# Dx32_V1_1.net
KiCad netlist of a schematic drawn in EAGLE
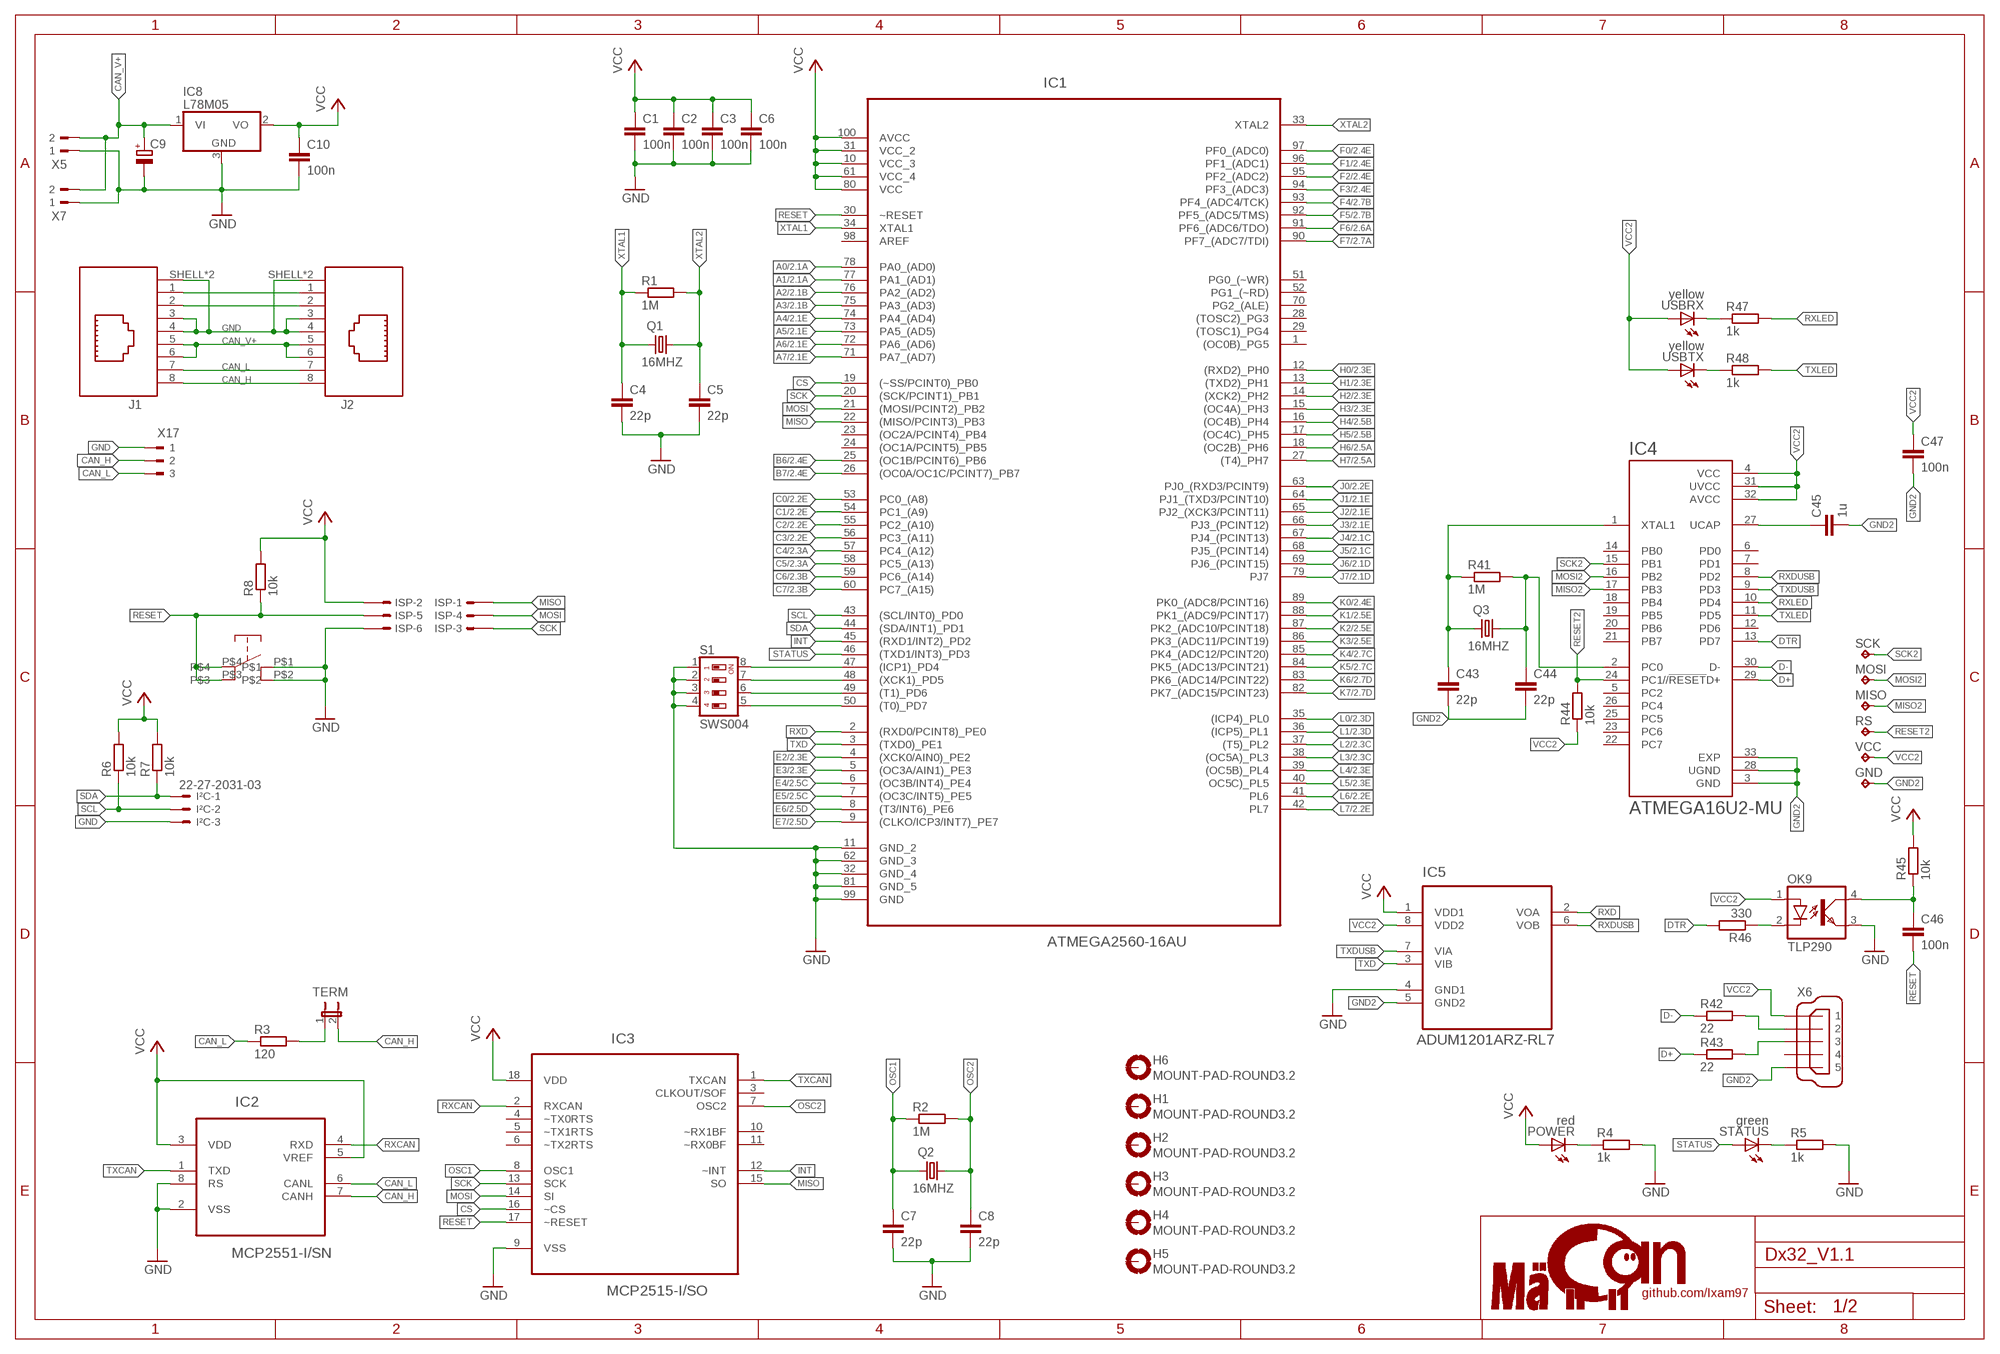
[diagram p0: schematic, sheet 1]
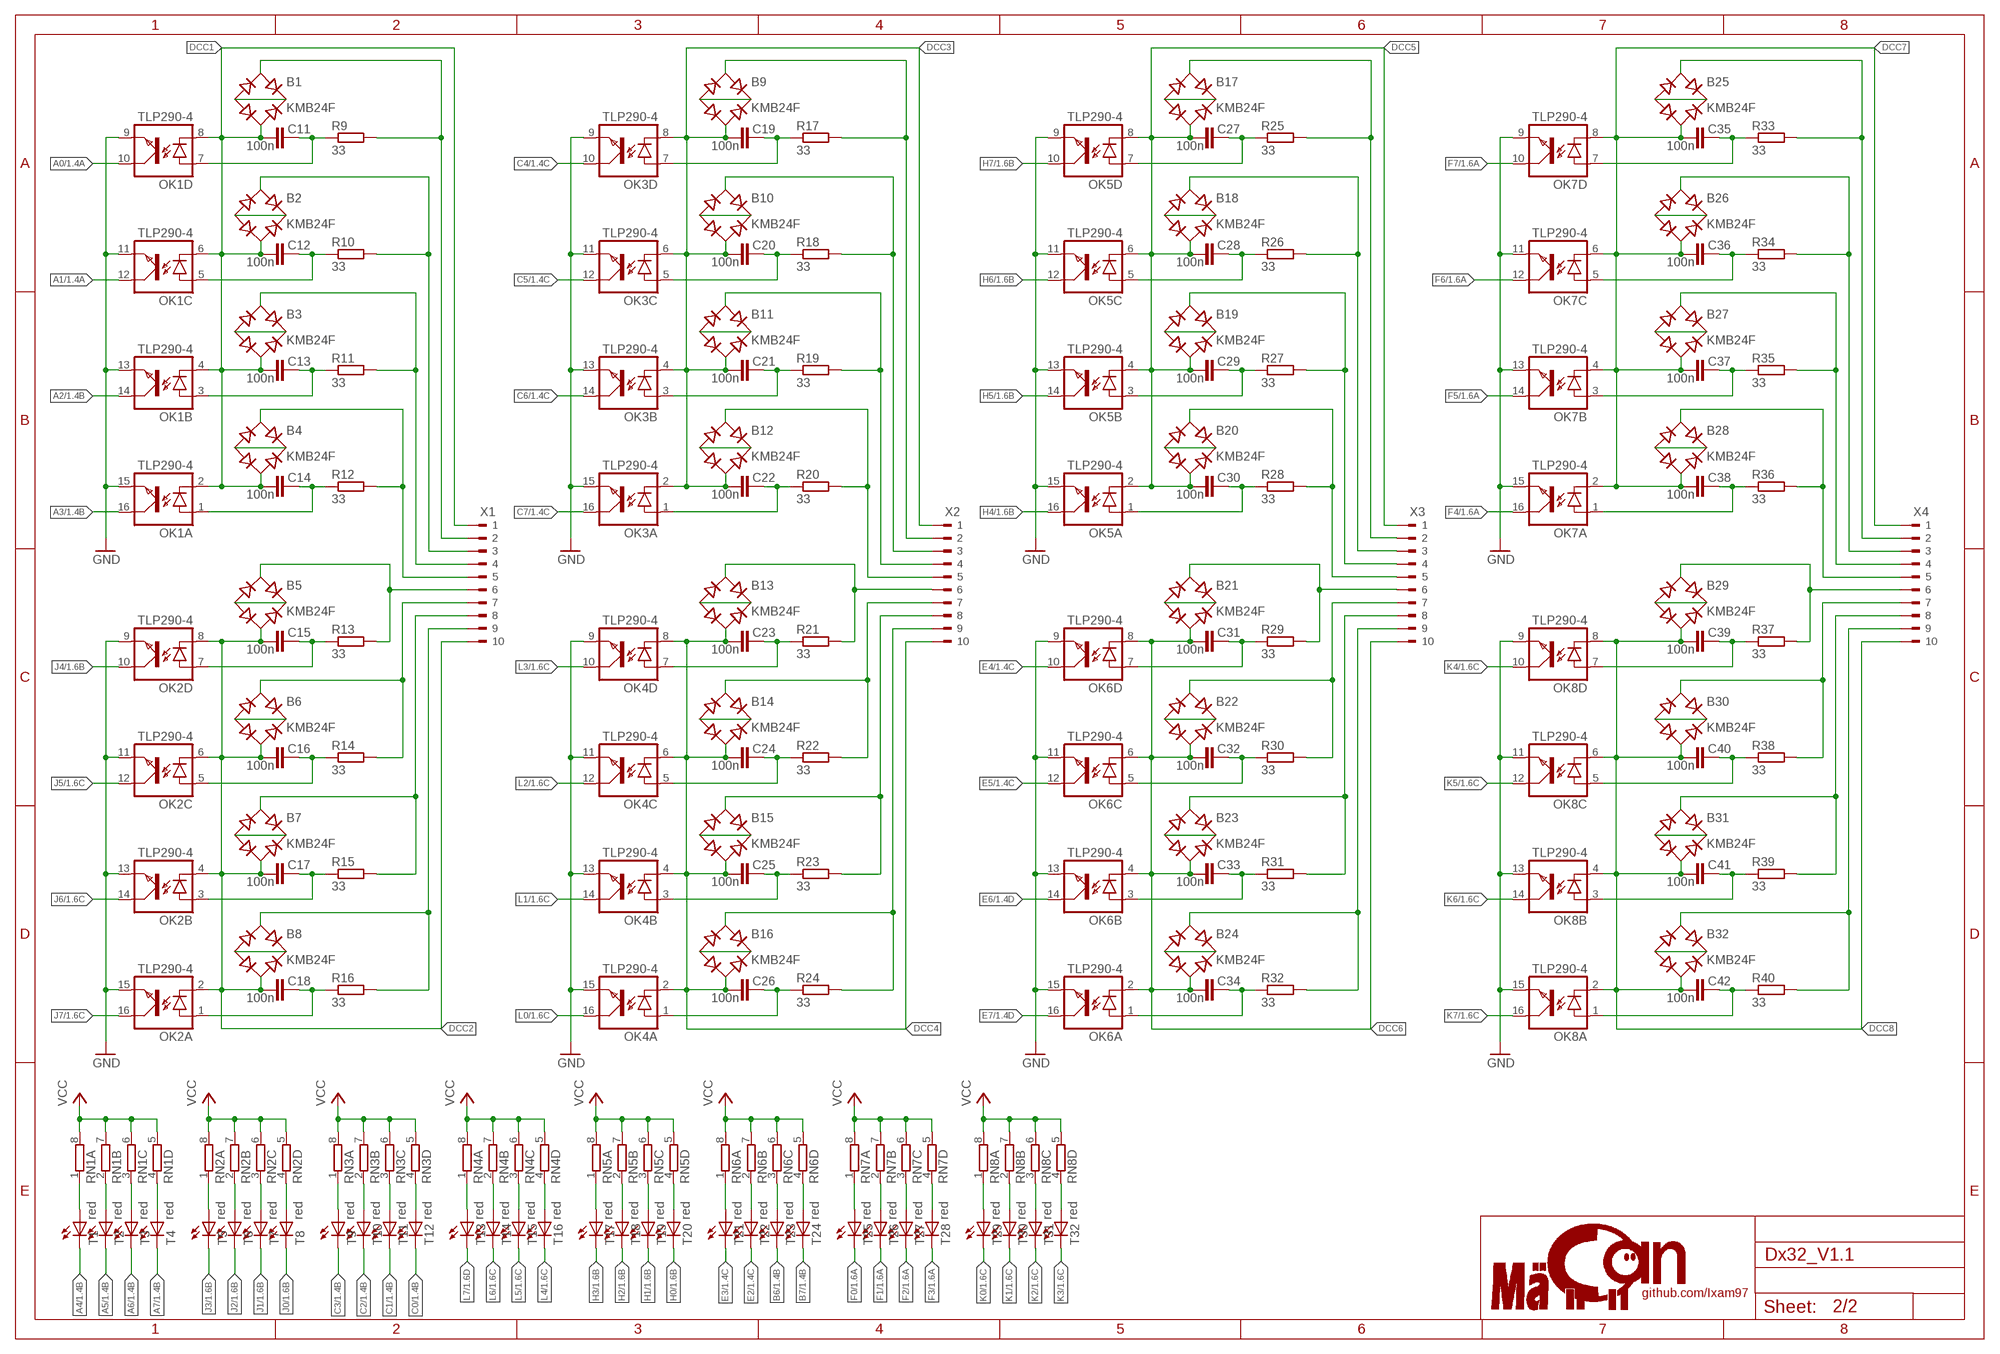
[diagram p1: schematic, sheet 2]

(export (version "E")
  (design (tool "Eeschema 10.0.6"))
  (components
    (comp (ref "B1")
      (value "KMB24F")
      (footprint "eagle-import:MBS")
      (fields (field (name "JLCPCB-PART") "C113927"))
      (libsource (lib "eagle-import") (part "BS2"))
    )
    (comp (ref "B2")
      (value "KMB24F")
      (footprint "eagle-import:MBS")
      (libsource (lib "eagle-import") (part "BS2"))
    )
    (comp (ref "B3")
      (value "KMB24F")
      (footprint "eagle-import:MBS")
      (libsource (lib "eagle-import") (part "BS2"))
    )
    (comp (ref "B4")
      (value "KMB24F")
      (footprint "eagle-import:MBS")
      (libsource (lib "eagle-import") (part "BS2"))
    )
    (comp (ref "B5")
      (value "KMB24F")
      (footprint "eagle-import:MBS")
      (libsource (lib "eagle-import") (part "BS2"))
    )
    (comp (ref "B6")
      (value "KMB24F")
      (footprint "eagle-import:MBS")
      (libsource (lib "eagle-import") (part "BS2"))
    )
    (comp (ref "B7")
      (value "KMB24F")
      (footprint "eagle-import:MBS")
      (libsource (lib "eagle-import") (part "BS2"))
    )
    (comp (ref "B8")
      (value "KMB24F")
      (footprint "eagle-import:MBS")
      (libsource (lib "eagle-import") (part "BS2"))
    )
    (comp (ref "B9")
      (value "KMB24F")
      (footprint "eagle-import:MBS")
      (libsource (lib "eagle-import") (part "BS2"))
    )
    (comp (ref "B10")
      (value "KMB24F")
      (footprint "eagle-import:MBS")
      (libsource (lib "eagle-import") (part "BS2"))
    )
    (comp (ref "B11")
      (value "KMB24F")
      (footprint "eagle-import:MBS")
      (libsource (lib "eagle-import") (part "BS2"))
    )
    (comp (ref "B12")
      (value "KMB24F")
      (footprint "eagle-import:MBS")
      (libsource (lib "eagle-import") (part "BS2"))
    )
    (comp (ref "B13")
      (value "KMB24F")
      (footprint "eagle-import:MBS")
      (libsource (lib "eagle-import") (part "BS2"))
    )
    (comp (ref "B14")
      (value "KMB24F")
      (footprint "eagle-import:MBS")
      (libsource (lib "eagle-import") (part "BS2"))
    )
    (comp (ref "B15")
      (value "KMB24F")
      (footprint "eagle-import:MBS")
      (libsource (lib "eagle-import") (part "BS2"))
    )
    (comp (ref "B16")
      (value "KMB24F")
      (footprint "eagle-import:MBS")
      (libsource (lib "eagle-import") (part "BS2"))
    )
    (comp (ref "B17")
      (value "KMB24F")
      (footprint "eagle-import:MBS")
      (libsource (lib "eagle-import") (part "BS2"))
    )
    (comp (ref "B18")
      (value "KMB24F")
      (footprint "eagle-import:MBS")
      (libsource (lib "eagle-import") (part "BS2"))
    )
    (comp (ref "B19")
      (value "KMB24F")
      (footprint "eagle-import:MBS")
      (libsource (lib "eagle-import") (part "BS2"))
    )
    (comp (ref "B20")
      (value "KMB24F")
      (footprint "eagle-import:MBS")
      (libsource (lib "eagle-import") (part "BS2"))
    )
    (comp (ref "B21")
      (value "KMB24F")
      (footprint "eagle-import:MBS")
      (libsource (lib "eagle-import") (part "BS2"))
    )
    (comp (ref "B22")
      (value "KMB24F")
      (footprint "eagle-import:MBS")
      (libsource (lib "eagle-import") (part "BS2"))
    )
    (comp (ref "B23")
      (value "KMB24F")
      (footprint "eagle-import:MBS")
      (libsource (lib "eagle-import") (part "BS2"))
    )
    (comp (ref "B24")
      (value "KMB24F")
      (footprint "eagle-import:MBS")
      (libsource (lib "eagle-import") (part "BS2"))
    )
    (comp (ref "B25")
      (value "KMB24F")
      (footprint "eagle-import:MBS")
      (libsource (lib "eagle-import") (part "BS2"))
    )
    (comp (ref "B26")
      (value "KMB24F")
      (footprint "eagle-import:MBS")
      (libsource (lib "eagle-import") (part "BS2"))
    )
    (comp (ref "B27")
      (value "KMB24F")
      (footprint "eagle-import:MBS")
      (libsource (lib "eagle-import") (part "BS2"))
    )
    (comp (ref "B28")
      (value "KMB24F")
      (footprint "eagle-import:MBS")
      (libsource (lib "eagle-import") (part "BS2"))
    )
    (comp (ref "B29")
      (value "KMB24F")
      (footprint "eagle-import:MBS")
      (libsource (lib "eagle-import") (part "BS2"))
    )
    (comp (ref "B30")
      (value "KMB24F")
      (footprint "eagle-import:MBS")
      (libsource (lib "eagle-import") (part "BS2"))
    )
    (comp (ref "B31")
      (value "KMB24F")
      (footprint "eagle-import:MBS")
      (libsource (lib "eagle-import") (part "BS2"))
    )
    (comp (ref "B32")
      (value "KMB24F")
      (footprint "eagle-import:MBS")
      (libsource (lib "eagle-import") (part "BS2"))
    )
    (comp (ref "C11")
      (value "100n")
      (footprint "eagle-import:C0402")
      (libsource (lib "eagle-import") (part "C-EUC0402"))
    )
    (comp (ref "C12")
      (value "100n")
      (footprint "eagle-import:C0402")
      (libsource (lib "eagle-import") (part "C-EUC0402"))
    )
    (comp (ref "C13")
      (value "100n")
      (footprint "eagle-import:C0402")
      (libsource (lib "eagle-import") (part "C-EUC0402"))
    )
    (comp (ref "C14")
      (value "100n")
      (footprint "eagle-import:C0402")
      (libsource (lib "eagle-import") (part "C-EUC0402"))
    )
    (comp (ref "C15")
      (value "100n")
      (footprint "eagle-import:C0402")
      (libsource (lib "eagle-import") (part "C-EUC0402"))
    )
    (comp (ref "C16")
      (value "100n")
      (footprint "eagle-import:C0402")
      (libsource (lib "eagle-import") (part "C-EUC0402"))
    )
    (comp (ref "C17")
      (value "100n")
      (footprint "eagle-import:C0402")
      (libsource (lib "eagle-import") (part "C-EUC0402"))
    )
    (comp (ref "C18")
      (value "100n")
      (footprint "eagle-import:C0402")
      (libsource (lib "eagle-import") (part "C-EUC0402"))
    )
    (comp (ref "C19")
      (value "100n")
      (footprint "eagle-import:C0402")
      (libsource (lib "eagle-import") (part "C-EUC0402"))
    )
    (comp (ref "C20")
      (value "100n")
      (footprint "eagle-import:C0402")
      (libsource (lib "eagle-import") (part "C-EUC0402"))
    )
    (comp (ref "C21")
      (value "100n")
      (footprint "eagle-import:C0402")
      (libsource (lib "eagle-import") (part "C-EUC0402"))
    )
    (comp (ref "C22")
      (value "100n")
      (footprint "eagle-import:C0402")
      (libsource (lib "eagle-import") (part "C-EUC0402"))
    )
    (comp (ref "C23")
      (value "100n")
      (footprint "eagle-import:C0402")
      (libsource (lib "eagle-import") (part "C-EUC0402"))
    )
    (comp (ref "C24")
      (value "100n")
      (footprint "eagle-import:C0402")
      (libsource (lib "eagle-import") (part "C-EUC0402"))
    )
    (comp (ref "C25")
      (value "100n")
      (footprint "eagle-import:C0402")
      (libsource (lib "eagle-import") (part "C-EUC0402"))
    )
    (comp (ref "C26")
      (value "100n")
      (footprint "eagle-import:C0402")
      (libsource (lib "eagle-import") (part "C-EUC0402"))
    )
    (comp (ref "C27")
      (value "100n")
      (footprint "eagle-import:C0402")
      (libsource (lib "eagle-import") (part "C-EUC0402"))
    )
    (comp (ref "C28")
      (value "100n")
      (footprint "eagle-import:C0402")
      (libsource (lib "eagle-import") (part "C-EUC0402"))
    )
    (comp (ref "C29")
      (value "100n")
      (footprint "eagle-import:C0402")
      (libsource (lib "eagle-import") (part "C-EUC0402"))
    )
    (comp (ref "C30")
      (value "100n")
      (footprint "eagle-import:C0402")
      (libsource (lib "eagle-import") (part "C-EUC0402"))
    )
    (comp (ref "C31")
      (value "100n")
      (footprint "eagle-import:C0402")
      (libsource (lib "eagle-import") (part "C-EUC0402"))
    )
    (comp (ref "C32")
      (value "100n")
      (footprint "eagle-import:C0402")
      (libsource (lib "eagle-import") (part "C-EUC0402"))
    )
    (comp (ref "C33")
      (value "100n")
      (footprint "eagle-import:C0402")
      (libsource (lib "eagle-import") (part "C-EUC0402"))
    )
    (comp (ref "C34")
      (value "100n")
      (footprint "eagle-import:C0402")
      (libsource (lib "eagle-import") (part "C-EUC0402"))
    )
    (comp (ref "C35")
      (value "100n")
      (footprint "eagle-import:C0402")
      (libsource (lib "eagle-import") (part "C-EUC0402"))
    )
    (comp (ref "C36")
      (value "100n")
      (footprint "eagle-import:C0402")
      (libsource (lib "eagle-import") (part "C-EUC0402"))
    )
    (comp (ref "C37")
      (value "100n")
      (footprint "eagle-import:C0402")
      (libsource (lib "eagle-import") (part "C-EUC0402"))
    )
    (comp (ref "C38")
      (value "100n")
      (footprint "eagle-import:C0402")
      (libsource (lib "eagle-import") (part "C-EUC0402"))
    )
    (comp (ref "C39")
      (value "100n")
      (footprint "eagle-import:C0402")
      (libsource (lib "eagle-import") (part "C-EUC0402"))
    )
    (comp (ref "C40")
      (value "100n")
      (footprint "eagle-import:C0402")
      (libsource (lib "eagle-import") (part "C-EUC0402"))
    )
    (comp (ref "C41")
      (value "100n")
      (footprint "eagle-import:C0402")
      (libsource (lib "eagle-import") (part "C-EUC0402"))
    )
    (comp (ref "C42")
      (value "100n")
      (footprint "eagle-import:C0402")
      (libsource (lib "eagle-import") (part "C-EUC0402"))
    )
    (comp (ref "OK1")
      (value "TLP290-4")
      (footprint "eagle-import:MINI-FLAT-16")
      (fields (field (name "JLCPC-PART") "C39031"))
      (libsource (lib "eagle-import") (part "TLP283-4"))
    )
    (comp (ref "OK2")
      (value "TLP290-4")
      (footprint "eagle-import:MINI-FLAT-16")
      (libsource (lib "eagle-import") (part "TLP283-4"))
    )
    (comp (ref "OK3")
      (value "TLP290-4")
      (footprint "eagle-import:MINI-FLAT-16")
      (libsource (lib "eagle-import") (part "TLP283-4"))
    )
    (comp (ref "OK4")
      (value "TLP290-4")
      (footprint "eagle-import:MINI-FLAT-16")
      (libsource (lib "eagle-import") (part "TLP283-4"))
    )
    (comp (ref "OK5")
      (value "TLP290-4")
      (footprint "eagle-import:MINI-FLAT-16")
      (libsource (lib "eagle-import") (part "TLP283-4"))
    )
    (comp (ref "OK6")
      (value "TLP290-4")
      (footprint "eagle-import:MINI-FLAT-16")
      (libsource (lib "eagle-import") (part "TLP283-4"))
    )
    (comp (ref "OK7")
      (value "TLP290-4")
      (footprint "eagle-import:MINI-FLAT-16")
      (libsource (lib "eagle-import") (part "TLP283-4"))
    )
    (comp (ref "OK8")
      (value "TLP290-4")
      (footprint "eagle-import:MINI-FLAT-16")
      (libsource (lib "eagle-import") (part "TLP283-4"))
    )
    (comp (ref "R9")
      (value "33")
      (footprint "eagle-import:R0402")
      (libsource (lib "eagle-import") (part "R-EU_R0402"))
    )
    (comp (ref "R10")
      (value "33")
      (footprint "eagle-import:R0402")
      (libsource (lib "eagle-import") (part "R-EU_R0402"))
    )
    (comp (ref "R11")
      (value "33")
      (footprint "eagle-import:R0402")
      (libsource (lib "eagle-import") (part "R-EU_R0402"))
    )
    (comp (ref "R12")
      (value "33")
      (footprint "eagle-import:R0402")
      (libsource (lib "eagle-import") (part "R-EU_R0402"))
    )
    (comp (ref "R13")
      (value "33")
      (footprint "eagle-import:R0402")
      (libsource (lib "eagle-import") (part "R-EU_R0402"))
    )
    (comp (ref "R14")
      (value "33")
      (footprint "eagle-import:R0402")
      (libsource (lib "eagle-import") (part "R-EU_R0402"))
    )
    (comp (ref "R15")
      (value "33")
      (footprint "eagle-import:R0402")
      (libsource (lib "eagle-import") (part "R-EU_R0402"))
    )
    (comp (ref "R16")
      (value "33")
      (footprint "eagle-import:R0402")
      (libsource (lib "eagle-import") (part "R-EU_R0402"))
    )
    (comp (ref "R17")
      (value "33")
      (footprint "eagle-import:R0402")
      (libsource (lib "eagle-import") (part "R-EU_R0402"))
    )
    (comp (ref "R18")
      (value "33")
      (footprint "eagle-import:R0402")
      (libsource (lib "eagle-import") (part "R-EU_R0402"))
    )
    (comp (ref "R19")
      (value "33")
      (footprint "eagle-import:R0402")
      (libsource (lib "eagle-import") (part "R-EU_R0402"))
    )
    (comp (ref "R20")
      (value "33")
      (footprint "eagle-import:R0402")
      (libsource (lib "eagle-import") (part "R-EU_R0402"))
    )
    (comp (ref "R21")
      (value "33")
      (footprint "eagle-import:R0402")
      (libsource (lib "eagle-import") (part "R-EU_R0402"))
    )
    (comp (ref "R22")
      (value "33")
      (footprint "eagle-import:R0402")
      (libsource (lib "eagle-import") (part "R-EU_R0402"))
    )
    (comp (ref "R23")
      (value "33")
      (footprint "eagle-import:R0402")
      (libsource (lib "eagle-import") (part "R-EU_R0402"))
    )
    (comp (ref "R24")
      (value "33")
      (footprint "eagle-import:R0402")
      (libsource (lib "eagle-import") (part "R-EU_R0402"))
    )
    (comp (ref "R25")
      (value "33")
      (footprint "eagle-import:R0402")
      (libsource (lib "eagle-import") (part "R-EU_R0402"))
    )
    (comp (ref "R26")
      (value "33")
      (footprint "eagle-import:R0402")
      (libsource (lib "eagle-import") (part "R-EU_R0402"))
    )
    (comp (ref "R27")
      (value "33")
      (footprint "eagle-import:R0402")
      (libsource (lib "eagle-import") (part "R-EU_R0402"))
    )
    (comp (ref "R28")
      (value "33")
      (footprint "eagle-import:R0402")
      (libsource (lib "eagle-import") (part "R-EU_R0402"))
    )
    (comp (ref "R29")
      (value "33")
      (footprint "eagle-import:R0402")
      (libsource (lib "eagle-import") (part "R-EU_R0402"))
    )
    (comp (ref "R30")
      (value "33")
      (footprint "eagle-import:R0402")
      (libsource (lib "eagle-import") (part "R-EU_R0402"))
    )
    (comp (ref "R31")
      (value "33")
      (footprint "eagle-import:R0402")
      (libsource (lib "eagle-import") (part "R-EU_R0402"))
    )
    (comp (ref "R32")
      (value "33")
      (footprint "eagle-import:R0402")
      (libsource (lib "eagle-import") (part "R-EU_R0402"))
    )
    (comp (ref "R33")
      (value "33")
      (footprint "eagle-import:R0402")
      (libsource (lib "eagle-import") (part "R-EU_R0402"))
    )
    (comp (ref "R34")
      (value "33")
      (footprint "eagle-import:R0402")
      (libsource (lib "eagle-import") (part "R-EU_R0402"))
    )
    (comp (ref "R35")
      (value "33")
      (footprint "eagle-import:R0402")
      (libsource (lib "eagle-import") (part "R-EU_R0402"))
    )
    (comp (ref "R36")
      (value "33")
      (footprint "eagle-import:R0402")
      (libsource (lib "eagle-import") (part "R-EU_R0402"))
    )
    (comp (ref "R37")
      (value "33")
      (footprint "eagle-import:R0402")
      (libsource (lib "eagle-import") (part "R-EU_R0402"))
    )
    (comp (ref "R38")
      (value "33")
      (footprint "eagle-import:R0402")
      (libsource (lib "eagle-import") (part "R-EU_R0402"))
    )
    (comp (ref "R39")
      (value "33")
      (footprint "eagle-import:R0402")
      (libsource (lib "eagle-import") (part "R-EU_R0402"))
    )
    (comp (ref "R40")
      (value "33")
      (footprint "eagle-import:R0402")
      (libsource (lib "eagle-import") (part "R-EU_R0402"))
    )
    (comp (ref "RN1")
      (value "4R-N0603-ARV")
      (footprint "eagle-import:0603-ARV")
      (libsource (lib "eagle-import") (part "4R-N0603-ARV"))
    )
    (comp (ref "RN2")
      (value "4R-N0603-ARV")
      (footprint "eagle-import:0603-ARV")
      (libsource (lib "eagle-import") (part "4R-N0603-ARV"))
    )
    (comp (ref "RN3")
      (value "4R-N0603-ARV")
      (footprint "eagle-import:0603-ARV")
      (libsource (lib "eagle-import") (part "4R-N0603-ARV"))
    )
    (comp (ref "RN4")
      (value "4R-N0603-ARV")
      (footprint "eagle-import:0603-ARV")
      (libsource (lib "eagle-import") (part "4R-N0603-ARV"))
    )
    (comp (ref "RN5")
      (value "4R-N0603-ARV")
      (footprint "eagle-import:0603-ARV")
      (libsource (lib "eagle-import") (part "4R-N0603-ARV"))
    )
    (comp (ref "RN6")
      (value "4R-N0603-ARV")
      (footprint "eagle-import:0603-ARV")
      (libsource (lib "eagle-import") (part "4R-N0603-ARV"))
    )
    (comp (ref "RN7")
      (value "4R-N0603-ARV")
      (footprint "eagle-import:0603-ARV")
      (libsource (lib "eagle-import") (part "4R-N0603-ARV"))
    )
    (comp (ref "RN8")
      (value "4R-N0603-ARV")
      (footprint "eagle-import:0603-ARV")
      (libsource (lib "eagle-import") (part "4R-N0603-ARV"))
    )
    (comp (ref "T1")
      (value "red")
      (footprint "eagle-import:CHIP-LED0805")
      (fields (field (name "JLCPCB-PART") "C84256"))
      (libsource (lib "eagle-import") (part "LEDCHIP-LED0805"))
    )
    (comp (ref "T2")
      (value "red")
      (footprint "eagle-import:CHIP-LED0805")
      (libsource (lib "eagle-import") (part "LEDCHIP-LED0805"))
    )
    (comp (ref "T3")
      (value "red")
      (footprint "eagle-import:CHIP-LED0805")
      (libsource (lib "eagle-import") (part "LEDCHIP-LED0805"))
    )
    (comp (ref "T4")
      (value "red")
      (footprint "eagle-import:CHIP-LED0805")
      (libsource (lib "eagle-import") (part "LEDCHIP-LED0805"))
    )
    (comp (ref "T5")
      (value "red")
      (footprint "eagle-import:CHIP-LED0805")
      (libsource (lib "eagle-import") (part "LEDCHIP-LED0805"))
    )
    (comp (ref "T6")
      (value "red")
      (footprint "eagle-import:CHIP-LED0805")
      (libsource (lib "eagle-import") (part "LEDCHIP-LED0805"))
    )
    (comp (ref "T7")
      (value "red")
      (footprint "eagle-import:CHIP-LED0805")
      (libsource (lib "eagle-import") (part "LEDCHIP-LED0805"))
    )
    (comp (ref "T8")
      (value "red")
      (footprint "eagle-import:CHIP-LED0805")
      (libsource (lib "eagle-import") (part "LEDCHIP-LED0805"))
    )
    (comp (ref "T9")
      (value "red")
      (footprint "eagle-import:CHIP-LED0805")
      (libsource (lib "eagle-import") (part "LEDCHIP-LED0805"))
    )
    (comp (ref "T10")
      (value "red")
      (footprint "eagle-import:CHIP-LED0805")
      (libsource (lib "eagle-import") (part "LEDCHIP-LED0805"))
    )
    (comp (ref "T11")
      (value "red")
      (footprint "eagle-import:CHIP-LED0805")
      (libsource (lib "eagle-import") (part "LEDCHIP-LED0805"))
    )
    (comp (ref "T12")
      (value "red")
      (footprint "eagle-import:CHIP-LED0805")
      (libsource (lib "eagle-import") (part "LEDCHIP-LED0805"))
    )
    (comp (ref "T13")
      (value "red")
      (footprint "eagle-import:CHIP-LED0805")
      (libsource (lib "eagle-import") (part "LEDCHIP-LED0805"))
    )
    (comp (ref "T14")
      (value "red")
      (footprint "eagle-import:CHIP-LED0805")
      (libsource (lib "eagle-import") (part "LEDCHIP-LED0805"))
    )
    (comp (ref "T15")
      (value "red")
      (footprint "eagle-import:CHIP-LED0805")
      (libsource (lib "eagle-import") (part "LEDCHIP-LED0805"))
    )
    (comp (ref "T16")
      (value "red")
      (footprint "eagle-import:CHIP-LED0805")
      (libsource (lib "eagle-import") (part "LEDCHIP-LED0805"))
    )
    (comp (ref "T17")
      (value "red")
      (footprint "eagle-import:CHIP-LED0805")
      (libsource (lib "eagle-import") (part "LEDCHIP-LED0805"))
    )
    (comp (ref "T18")
      (value "red")
      (footprint "eagle-import:CHIP-LED0805")
      (libsource (lib "eagle-import") (part "LEDCHIP-LED0805"))
    )
    (comp (ref "T19")
      (value "red")
      (footprint "eagle-import:CHIP-LED0805")
      (libsource (lib "eagle-import") (part "LEDCHIP-LED0805"))
    )
    (comp (ref "T20")
      (value "red")
      (footprint "eagle-import:CHIP-LED0805")
      (libsource (lib "eagle-import") (part "LEDCHIP-LED0805"))
    )
    (comp (ref "T21")
      (value "red")
      (footprint "eagle-import:CHIP-LED0805")
      (libsource (lib "eagle-import") (part "LEDCHIP-LED0805"))
    )
    (comp (ref "T22")
      (value "red")
      (footprint "eagle-import:CHIP-LED0805")
      (libsource (lib "eagle-import") (part "LEDCHIP-LED0805"))
    )
    (comp (ref "T23")
      (value "red")
      (footprint "eagle-import:CHIP-LED0805")
      (libsource (lib "eagle-import") (part "LEDCHIP-LED0805"))
    )
    (comp (ref "T24")
      (value "red")
      (footprint "eagle-import:CHIP-LED0805")
      (libsource (lib "eagle-import") (part "LEDCHIP-LED0805"))
    )
    (comp (ref "T25")
      (value "red")
      (footprint "eagle-import:CHIP-LED0805")
      (libsource (lib "eagle-import") (part "LEDCHIP-LED0805"))
    )
    (comp (ref "T26")
      (value "red")
      (footprint "eagle-import:CHIP-LED0805")
      (libsource (lib "eagle-import") (part "LEDCHIP-LED0805"))
    )
    (comp (ref "T27")
      (value "red")
      (footprint "eagle-import:CHIP-LED0805")
      (libsource (lib "eagle-import") (part "LEDCHIP-LED0805"))
    )
    (comp (ref "T28")
      (value "red")
      (footprint "eagle-import:CHIP-LED0805")
      (libsource (lib "eagle-import") (part "LEDCHIP-LED0805"))
    )
    (comp (ref "T29")
      (value "red")
      (footprint "eagle-import:CHIP-LED0805")
      (libsource (lib "eagle-import") (part "LEDCHIP-LED0805"))
    )
    (comp (ref "T30")
      (value "red")
      (footprint "eagle-import:CHIP-LED0805")
      (libsource (lib "eagle-import") (part "LEDCHIP-LED0805"))
    )
    (comp (ref "T31")
      (value "red")
      (footprint "eagle-import:CHIP-LED0805")
      (libsource (lib "eagle-import") (part "LEDCHIP-LED0805"))
    )
    (comp (ref "T32")
      (value "red")
      (footprint "eagle-import:CHIP-LED0805")
      (libsource (lib "eagle-import") (part "LEDCHIP-LED0805"))
    )
    (comp (ref "X1")
      (value "180-10")
      (footprint "eagle-import:180-10")
      (libsource (lib "eagle-import") (part "180-10"))
    )
    (comp (ref "X2")
      (value "180-10")
      (footprint "eagle-import:180-10")
      (libsource (lib "eagle-import") (part "180-10"))
    )
    (comp (ref "X3")
      (value "180-10")
      (footprint "eagle-import:180-10")
      (libsource (lib "eagle-import") (part "180-10"))
    )
    (comp (ref "X4")
      (value "180-10")
      (footprint "eagle-import:180-10")
      (libsource (lib "eagle-import") (part "180-10"))
    )
    (comp (ref "C1")
      (value "100n")
      (footprint "eagle-import:C0402")
      (libsource (lib "eagle-import") (part "C-EUC0402"))
    )
    (comp (ref "C2")
      (value "100n")
      (footprint "eagle-import:C0402")
      (libsource (lib "eagle-import") (part "C-EUC0402"))
    )
    (comp (ref "C3")
      (value "100n")
      (footprint "eagle-import:C0402")
      (libsource (lib "eagle-import") (part "C-EUC0402"))
    )
    (comp (ref "C4")
      (value "22p")
      (footprint "eagle-import:C0402")
      (libsource (lib "eagle-import") (part "C-EUC0402"))
    )
    (comp (ref "C5")
      (value "22p")
      (footprint "eagle-import:C0402")
      (libsource (lib "eagle-import") (part "C-EUC0402"))
    )
    (comp (ref "C6")
      (value "100n")
      (footprint "eagle-import:C0402")
      (libsource (lib "eagle-import") (part "C-EUC0402"))
    )
    (comp (ref "C7")
      (value "22p")
      (footprint "eagle-import:C0402")
      (libsource (lib "eagle-import") (part "C-EUC0402"))
    )
    (comp (ref "C8")
      (value "22p")
      (footprint "eagle-import:C0402")
      (libsource (lib "eagle-import") (part "C-EUC0402"))
    )
    (comp (ref "C9")
      (value "CPOL-EUCT3216")
      (footprint "eagle-import:CT3216")
      (libsource (lib "eagle-import") (part "CPOL-EUCT3216"))
    )
    (comp (ref "C10")
      (value "100n")
      (footprint "eagle-import:C0402")
      (libsource (lib "eagle-import") (part "C-EUC0402"))
    )
    (comp (ref "C43")
      (value "22p")
      (footprint "eagle-import:C0402")
      (libsource (lib "eagle-import") (part "C-EUC0402"))
    )
    (comp (ref "C44")
      (value "22p")
      (footprint "eagle-import:C0402")
      (libsource (lib "eagle-import") (part "C-EUC0402"))
    )
    (comp (ref "C45")
      (value "1u")
      (footprint "eagle-import:C0402")
      (libsource (lib "eagle-import") (part "C-EUC0402"))
    )
    (comp (ref "C46")
      (value "100n")
      (footprint "eagle-import:C0402")
      (libsource (lib "eagle-import") (part "C-EUC0402"))
    )
    (comp (ref "C47")
      (value "100n")
      (footprint "eagle-import:C0402")
      (libsource (lib "eagle-import") (part "C-EUC0402"))
    )
    (comp (ref "GND")
      (value "TPB1,27")
      (footprint "eagle-import:B1,27")
      (libsource (lib "eagle-import") (part "TPB1,27"))
    )
    (comp (ref "H1")
      (value "MOUNT-PAD-ROUND3.2")
      (footprint "eagle-import:3,2-PAD")
      (libsource (lib "eagle-import") (part "MOUNT-PAD-ROUND3.2"))
    )
    (comp (ref "H2")
      (value "MOUNT-PAD-ROUND3.2")
      (footprint "eagle-import:3,2-PAD")
      (libsource (lib "eagle-import") (part "MOUNT-PAD-ROUND3.2"))
    )
    (comp (ref "H3")
      (value "MOUNT-PAD-ROUND3.2")
      (footprint "eagle-import:3,2-PAD")
      (libsource (lib "eagle-import") (part "MOUNT-PAD-ROUND3.2"))
    )
    (comp (ref "H4")
      (value "MOUNT-PAD-ROUND3.2")
      (footprint "eagle-import:3,2-PAD")
      (libsource (lib "eagle-import") (part "MOUNT-PAD-ROUND3.2"))
    )
    (comp (ref "H5")
      (value "MOUNT-PAD-ROUND3.2")
      (footprint "eagle-import:3,2-PAD")
      (libsource (lib "eagle-import") (part "MOUNT-PAD-ROUND3.2"))
    )
    (comp (ref "H6")
      (value "MOUNT-PAD-ROUND3.2")
      (footprint "eagle-import:3,2-PAD")
      (libsource (lib "eagle-import") (part "MOUNT-PAD-ROUND3.2"))
    )
    (comp (ref "IC1")
      (value "ATMEGA2560-16AU")
      (footprint "eagle-import:QFP50P1600X1600X120-100N")
      (fields (field (name "MF") "Microchip"))
      (libsource (lib "eagle-import") (part "ATMEGA2560-16AU"))
    )
    (comp (ref "IC2")
      (value "MCP2551-I/SN")
      (footprint "eagle-import:SOIC127P600X175-8N")
      (libsource (lib "eagle-import") (part "MCP2551-I/SN"))
    )
    (comp (ref "IC3")
      (value "MCP2515-I/SO")
      (footprint "eagle-import:SOIC127P1034X264-18N")
      (libsource (lib "eagle-import") (part "MCP2515-I/SO"))
    )
    (comp (ref "IC4")
      (value "ATMEGA16U2-MU")
      (footprint "eagle-import:QFN50P500X500X100-33N")
      (fields (field (name "MF") "Microchip"))
      (libsource (lib "eagle-import") (part "ATMEGA16U2-MU"))
    )
    (comp (ref "IC5")
      (value "ADUM1201ARZ-RL7")
      (footprint "eagle-import:SOIC127P600X175-8N")
      (fields (field (name "MF") "Analog Devices"))
      (libsource (lib "eagle-import") (part "ADUM1201ARZ-RL7"))
    )
    (comp (ref "IC8")
      (value "L78M05")
      (footprint "eagle-import:TO252")
      (fields (field (name "JLCPCB-PART") "C58069"))
      (libsource (lib "eagle-import") (part "78DT05"))
    )
    (comp (ref "ISP")
      (value "057-006-1")
      (footprint "eagle-import:057-006-1")
      (libsource (lib "eagle-import") (part "057-006-1"))
    )
    (comp (ref "I²C")
      (value "22-27-2031-03")
      (footprint "eagle-import:6410-03")
      (fields (field (name "MF") "MOLEX"))
      (libsource (lib "eagle-import") (part "22-?-0327-2031"))
    )
    (comp (ref "J1")
      (value "615008140421")
      (footprint "eagle-import:615008140421")
      (libsource (lib "eagle-import") (part "615008140421"))
    )
    (comp (ref "J2")
      (value "615008140421")
      (footprint "eagle-import:615008140421")
      (libsource (lib "eagle-import") (part "615008140421"))
    )
    (comp (ref "MISO")
      (value "TPB1,27")
      (footprint "eagle-import:B1,27")
      (libsource (lib "eagle-import") (part "TPB1,27"))
    )
    (comp (ref "MOSI")
      (value "TPB1,27")
      (footprint "eagle-import:B1,27")
      (libsource (lib "eagle-import") (part "TPB1,27"))
    )
    (comp (ref "OK9")
      (value "TLP290")
      (footprint "eagle-import:MINI-FLAT-4")
      (libsource (lib "eagle-import") (part "TLP283"))
    )
    (comp (ref "POWER")
      (value "red")
      (footprint "eagle-import:CHIP-LED0805")
      (libsource (lib "eagle-import") (part "LEDCHIP-LED0805"))
    )
    (comp (ref "Q1")
      (value "16MHZ")
      (footprint "eagle-import:3.2X2.5_KX-7")
      (libsource (lib "eagle-import") (part "KX-7"))
    )
    (comp (ref "Q2")
      (value "16MHZ")
      (footprint "eagle-import:3.2X2.5_KX-7")
      (libsource (lib "eagle-import") (part "KX-7"))
    )
    (comp (ref "Q3")
      (value "16MHZ")
      (footprint "eagle-import:3.2X2.5_KX-7")
      (libsource (lib "eagle-import") (part "KX-7"))
    )
    (comp (ref "R1")
      (value "1M")
      (footprint "eagle-import:R0402")
      (libsource (lib "eagle-import") (part "R-EU_R0402"))
    )
    (comp (ref "R2")
      (value "1M")
      (footprint "eagle-import:R0402")
      (libsource (lib "eagle-import") (part "R-EU_R0402"))
    )
    (comp (ref "R3")
      (value "120")
      (footprint "eagle-import:R0402")
      (libsource (lib "eagle-import") (part "R-EU_R0402"))
    )
    (comp (ref "R4")
      (value "1k")
      (footprint "eagle-import:R0402")
      (libsource (lib "eagle-import") (part "R-EU_R0402"))
    )
    (comp (ref "R5")
      (value "1k")
      (footprint "eagle-import:R0402")
      (libsource (lib "eagle-import") (part "R-EU_R0402"))
    )
    (comp (ref "R6")
      (value "10k")
      (footprint "eagle-import:R0402")
      (libsource (lib "eagle-import") (part "R-EU_R0402"))
    )
    (comp (ref "R7")
      (value "10k")
      (footprint "eagle-import:R0402")
      (libsource (lib "eagle-import") (part "R-EU_R0402"))
    )
    (comp (ref "R8")
      (value "10k")
      (footprint "eagle-import:R0402")
      (libsource (lib "eagle-import") (part "R-EU_R0402"))
    )
    (comp (ref "R41")
      (value "1M")
      (footprint "eagle-import:R0402")
      (libsource (lib "eagle-import") (part "R-EU_R0402"))
    )
    (comp (ref "R42")
      (value "22")
      (footprint "eagle-import:R0402")
      (libsource (lib "eagle-import") (part "R-EU_R0402"))
    )
    (comp (ref "R43")
      (value "22")
      (footprint "eagle-import:R0402")
      (libsource (lib "eagle-import") (part "R-EU_R0402"))
    )
    (comp (ref "R44")
      (value "10k")
      (footprint "eagle-import:R0402")
      (libsource (lib "eagle-import") (part "R-EU_R0402"))
    )
    (comp (ref "R45")
      (value "10k")
      (footprint "eagle-import:R0402")
      (libsource (lib "eagle-import") (part "R-EU_R0402"))
    )
    (comp (ref "R46")
      (value "330")
      (footprint "eagle-import:R0402")
      (libsource (lib "eagle-import") (part "R-EU_R0402"))
    )
    (comp (ref "R47")
      (value "1k")
      (footprint "eagle-import:R0402")
      (libsource (lib "eagle-import") (part "R-EU_R0402"))
    )
    (comp (ref "R48")
      (value "1k")
      (footprint "eagle-import:R0402")
      (libsource (lib "eagle-import") (part "R-EU_R0402"))
    )
    (comp (ref "RS")
      (value "TPB1,27")
      (footprint "eagle-import:B1,27")
      (libsource (lib "eagle-import") (part "TPB1,27"))
    )
    (comp (ref "S1")
      (value "SWS004")
      (footprint "eagle-import:SMS-004")
      (libsource (lib "eagle-import") (part "SWS004"))
    )
    (comp (ref "SCK")
      (value "TPB1,27")
      (footprint "eagle-import:B1,27")
      (libsource (lib "eagle-import") (part "TPB1,27"))
    )
    (comp (ref "STATUS")
      (value "green")
      (footprint "eagle-import:CHIP-LED0805")
      (libsource (lib "eagle-import") (part "LEDCHIP-LED0805"))
    )
    (comp (ref "TERM")
      (value "JP1E")
      (footprint "eagle-import:JP1")
      (libsource (lib "eagle-import") (part "JP1E"))
    )
    (comp (ref "U$15")
      (value "BUTTON_JLC")
      (footprint "eagle-import:BUTTON")
      (libsource (lib "eagle-import") (part "BUTTON_JLC"))
    )
    (comp (ref "USBRX")
      (value "yellow")
      (footprint "eagle-import:CHIP-LED0805")
      (libsource (lib "eagle-import") (part "LEDCHIP-LED0805"))
    )
    (comp (ref "USBTX")
      (value "yellow")
      (footprint "eagle-import:CHIP-LED0805")
      (libsource (lib "eagle-import") (part "LEDCHIP-LED0805"))
    )
    (comp (ref "VCC")
      (value "TPB1,27")
      (footprint "eagle-import:B1,27")
      (libsource (lib "eagle-import") (part "TPB1,27"))
    )
    (comp (ref "X5")
      (value "180-2")
      (footprint "eagle-import:180-2")
      (libsource (lib "eagle-import") (part "180-2"))
    )
    (comp (ref "X6")
      (value "MINI-USB_SHIELD5P2-32005-601")
      (footprint "eagle-import:32005-601")
      (libsource (lib "eagle-import") (part "MINI-USB_SHIELD5P2-32005-601"))
    )
    (comp (ref "X7")
      (value "180-2")
      (footprint "eagle-import:180-2")
      (libsource (lib "eagle-import") (part "180-2"))
    )
    (comp (ref "X17")
      (value "180-3")
      (footprint "eagle-import:180-3")
      (libsource (lib "eagle-import") (part "180-3"))
    )
  )
  (nets
    (net (code "1") (name "A0") (class "Default")
      (node (ref "IC1") (pin "78") (pinfunction "PA0_(AD0)_78") (pintype "bidirectional"))
      (node (ref "OK1") (pin "10") (pinfunction "COL_10") (pintype "passive"))
    )
    (net (code "2") (name "A1") (class "Default")
      (node (ref "IC1") (pin "77") (pinfunction "PA1_(AD1)_77") (pintype "bidirectional"))
      (node (ref "OK1") (pin "12") (pinfunction "COL_12") (pintype "passive"))
    )
    (net (code "3") (name "A2") (class "Default")
      (node (ref "IC1") (pin "76") (pinfunction "PA2_(AD2)_76") (pintype "bidirectional"))
      (node (ref "OK1") (pin "14") (pinfunction "COL_14") (pintype "passive"))
    )
    (net (code "4") (name "A3") (class "Default")
      (node (ref "IC1") (pin "75") (pinfunction "PA3_(AD3)_75") (pintype "bidirectional"))
      (node (ref "OK1") (pin "16") (pinfunction "COL_16") (pintype "passive"))
    )
    (net (code "5") (name "A4") (class "Default")
      (node (ref "IC1") (pin "74") (pinfunction "PA4_(AD4)_74") (pintype "bidirectional"))
      (node (ref "T1") (pin "C") (pinfunction "C_C") (pintype "passive"))
    )
    (net (code "6") (name "A5") (class "Default")
      (node (ref "IC1") (pin "73") (pinfunction "PA5_(AD5)_73") (pintype "bidirectional"))
      (node (ref "T2") (pin "C") (pinfunction "C_C") (pintype "passive"))
    )
    (net (code "7") (name "A6") (class "Default")
      (node (ref "IC1") (pin "72") (pinfunction "PA6_(AD6)_72") (pintype "bidirectional"))
      (node (ref "T3") (pin "C") (pinfunction "C_C") (pintype "passive"))
    )
    (net (code "8") (name "A7") (class "Default")
      (node (ref "IC1") (pin "71") (pinfunction "PA7_(AD7)_71") (pintype "bidirectional"))
      (node (ref "T4") (pin "C") (pinfunction "C_C") (pintype "passive"))
    )
    (net (code "9") (name "B6") (class "Default")
      (node (ref "IC1") (pin "25") (pinfunction "(OC1B/PCINT6)_PB6_25") (pintype "bidirectional"))
      (node (ref "T23") (pin "C") (pinfunction "C_C") (pintype "passive"))
    )
    (net (code "10") (name "B7") (class "Default")
      (node (ref "IC1") (pin "26") (pinfunction "(OC0A/OC1C/PCINT7)_PB7_26") (pintype "bidirectional"))
      (node (ref "T24") (pin "C") (pinfunction "C_C") (pintype "passive"))
    )
    (net (code "11") (name "C0") (class "Default")
      (node (ref "IC1") (pin "53") (pinfunction "PC0_(A8)_53") (pintype "bidirectional"))
      (node (ref "T12") (pin "C") (pinfunction "C_C") (pintype "passive"))
    )
    (net (code "12") (name "C1") (class "Default")
      (node (ref "IC1") (pin "54") (pinfunction "PC1_(A9)_54") (pintype "bidirectional"))
      (node (ref "T11") (pin "C") (pinfunction "C_C") (pintype "passive"))
    )
    (net (code "13") (name "C2") (class "Default")
      (node (ref "IC1") (pin "55") (pinfunction "PC2_(A10)_55") (pintype "bidirectional"))
      (node (ref "T10") (pin "C") (pinfunction "C_C") (pintype "passive"))
    )
    (net (code "14") (name "C3") (class "Default")
      (node (ref "IC1") (pin "56") (pinfunction "PC3_(A11)_56") (pintype "bidirectional"))
      (node (ref "T9") (pin "C") (pinfunction "C_C") (pintype "passive"))
    )
    (net (code "15") (name "C4") (class "Default")
      (node (ref "IC1") (pin "57") (pinfunction "PC4_(A12)_57") (pintype "bidirectional"))
      (node (ref "OK3") (pin "10") (pinfunction "COL_10") (pintype "passive"))
    )
    (net (code "16") (name "C5") (class "Default")
      (node (ref "IC1") (pin "58") (pinfunction "PC5_(A13)_58") (pintype "bidirectional"))
      (node (ref "OK3") (pin "12") (pinfunction "COL_12") (pintype "passive"))
    )
    (net (code "17") (name "C6") (class "Default")
      (node (ref "IC1") (pin "59") (pinfunction "PC6_(A14)_59") (pintype "bidirectional"))
      (node (ref "OK3") (pin "14") (pinfunction "COL_14") (pintype "passive"))
    )
    (net (code "18") (name "C7") (class "Default")
      (node (ref "IC1") (pin "60") (pinfunction "PC7_(A15)_60") (pintype "bidirectional"))
      (node (ref "OK3") (pin "16") (pinfunction "COL_16") (pintype "passive"))
    )
    (net (code "19") (name "CAN_H") (class "Default")
      (node (ref "IC2") (pin "7") (pinfunction "CANH_7") (pintype "bidirectional"))
      (node (ref "J1") (pin "8") (pinfunction "8_8") (pintype "passive"))
      (node (ref "J2") (pin "8") (pinfunction "8_8") (pintype "passive"))
      (node (ref "TERM") (pin "2") (pinfunction "2_2") (pintype "passive"))
      (node (ref "X17") (pin "2") (pinfunction "2_2") (pintype "passive"))
    )
    (net (code "20") (name "CAN_L") (class "Default")
      (node (ref "IC2") (pin "6") (pinfunction "CANL_6") (pintype "bidirectional"))
      (node (ref "J1") (pin "7") (pinfunction "7_7") (pintype "passive"))
      (node (ref "J2") (pin "7") (pinfunction "7_7") (pintype "passive"))
      (node (ref "R3") (pin "1") (pinfunction "1_1") (pintype "passive"))
      (node (ref "X17") (pin "3") (pinfunction "3_3") (pintype "passive"))
    )
    (net (code "21") (name "CAN_V+") (class "Default")
      (node (ref "C9") (pin "+") (pinfunction "+_+") (pintype "passive"))
      (node (ref "IC8") (pin "1") (pinfunction "VI_1") (pintype "input"))
      (node (ref "J1") (pin "5") (pinfunction "5_5") (pintype "passive"))
      (node (ref "J1") (pin "6") (pinfunction "6_6") (pintype "passive"))
      (node (ref "J2") (pin "5") (pinfunction "5_5") (pintype "passive"))
      (node (ref "J2") (pin "6") (pinfunction "6_6") (pintype "passive"))
      (node (ref "X5") (pin "2") (pinfunction "2_2") (pintype "passive"))
      (node (ref "X7") (pin "2") (pinfunction "2_2") (pintype "passive"))
    )
    (net (code "22") (name "CS") (class "Default")
      (node (ref "IC1") (pin "19") (pinfunction "(~{SS/PCINT0})_PB0_19") (pintype "bidirectional"))
      (node (ref "IC3") (pin "16") (pinfunction "~{CS}_16") (pintype "input"))
    )
    (net (code "23") (name "D+") (class "Default")
      (node (ref "IC4") (pin "29") (pinfunction "D+_29") (pintype "bidirectional"))
      (node (ref "R43") (pin "1") (pinfunction "1_1") (pintype "passive"))
    )
    (net (code "24") (name "D-") (class "Default")
      (node (ref "IC4") (pin "30") (pinfunction "D-_30") (pintype "bidirectional"))
      (node (ref "R42") (pin "1") (pinfunction "1_1") (pintype "passive"))
    )
    (net (code "25") (name "DCC1") (class "Default")
      (node (ref "B1") (pin "AC2") (pinfunction "AC2_AC2") (pintype "passive"))
      (node (ref "B2") (pin "AC2") (pinfunction "AC2_AC2") (pintype "passive"))
      (node (ref "B3") (pin "AC2") (pinfunction "AC2_AC2") (pintype "passive"))
      (node (ref "B4") (pin "AC2") (pinfunction "AC2_AC2") (pintype "passive"))
      (node (ref "C11") (pin "2") (pinfunction "2_2") (pintype "passive"))
      (node (ref "C12") (pin "2") (pinfunction "2_2") (pintype "passive"))
      (node (ref "C13") (pin "2") (pinfunction "2_2") (pintype "passive"))
      (node (ref "C14") (pin "2") (pinfunction "2_2") (pintype "passive"))
      (node (ref "OK1") (pin "2") (pinfunction "C_2") (pintype "passive"))
      (node (ref "OK1") (pin "4") (pinfunction "C_4") (pintype "passive"))
      (node (ref "OK1") (pin "6") (pinfunction "C_6") (pintype "passive"))
      (node (ref "OK1") (pin "8") (pinfunction "C_8") (pintype "passive"))
      (node (ref "X1") (pin "1") (pinfunction "1_1") (pintype "passive"))
    )
    (net (code "26") (name "DCC2") (class "Default")
      (node (ref "B5") (pin "AC2") (pinfunction "AC2_AC2") (pintype "passive"))
      (node (ref "B6") (pin "AC2") (pinfunction "AC2_AC2") (pintype "passive"))
      (node (ref "B7") (pin "AC2") (pinfunction "AC2_AC2") (pintype "passive"))
      (node (ref "B8") (pin "AC2") (pinfunction "AC2_AC2") (pintype "passive"))
      (node (ref "C15") (pin "2") (pinfunction "2_2") (pintype "passive"))
      (node (ref "C16") (pin "2") (pinfunction "2_2") (pintype "passive"))
      (node (ref "C17") (pin "2") (pinfunction "2_2") (pintype "passive"))
      (node (ref "C18") (pin "2") (pinfunction "2_2") (pintype "passive"))
      (node (ref "OK2") (pin "2") (pinfunction "C_2") (pintype "passive"))
      (node (ref "OK2") (pin "4") (pinfunction "C_4") (pintype "passive"))
      (node (ref "OK2") (pin "6") (pinfunction "C_6") (pintype "passive"))
      (node (ref "OK2") (pin "8") (pinfunction "C_8") (pintype "passive"))
      (node (ref "X1") (pin "10") (pinfunction "10_10") (pintype "passive"))
    )
    (net (code "27") (name "DCC3") (class "Default")
      (node (ref "B10") (pin "AC2") (pinfunction "AC2_AC2") (pintype "passive"))
      (node (ref "B11") (pin "AC2") (pinfunction "AC2_AC2") (pintype "passive"))
      (node (ref "B12") (pin "AC2") (pinfunction "AC2_AC2") (pintype "passive"))
      (node (ref "B9") (pin "AC2") (pinfunction "AC2_AC2") (pintype "passive"))
      (node (ref "C19") (pin "2") (pinfunction "2_2") (pintype "passive"))
      (node (ref "C20") (pin "2") (pinfunction "2_2") (pintype "passive"))
      (node (ref "C21") (pin "2") (pinfunction "2_2") (pintype "passive"))
      (node (ref "C22") (pin "2") (pinfunction "2_2") (pintype "passive"))
      (node (ref "OK3") (pin "2") (pinfunction "C_2") (pintype "passive"))
      (node (ref "OK3") (pin "4") (pinfunction "C_4") (pintype "passive"))
      (node (ref "OK3") (pin "6") (pinfunction "C_6") (pintype "passive"))
      (node (ref "OK3") (pin "8") (pinfunction "C_8") (pintype "passive"))
      (node (ref "X2") (pin "1") (pinfunction "1_1") (pintype "passive"))
    )
    (net (code "28") (name "DCC4") (class "Default")
      (node (ref "B13") (pin "AC2") (pinfunction "AC2_AC2") (pintype "passive"))
      (node (ref "B14") (pin "AC2") (pinfunction "AC2_AC2") (pintype "passive"))
      (node (ref "B15") (pin "AC2") (pinfunction "AC2_AC2") (pintype "passive"))
      (node (ref "B16") (pin "AC2") (pinfunction "AC2_AC2") (pintype "passive"))
      (node (ref "C23") (pin "2") (pinfunction "2_2") (pintype "passive"))
      (node (ref "C24") (pin "2") (pinfunction "2_2") (pintype "passive"))
      (node (ref "C25") (pin "2") (pinfunction "2_2") (pintype "passive"))
      (node (ref "C26") (pin "2") (pinfunction "2_2") (pintype "passive"))
      (node (ref "OK4") (pin "2") (pinfunction "C_2") (pintype "passive"))
      (node (ref "OK4") (pin "4") (pinfunction "C_4") (pintype "passive"))
      (node (ref "OK4") (pin "6") (pinfunction "C_6") (pintype "passive"))
      (node (ref "OK4") (pin "8") (pinfunction "C_8") (pintype "passive"))
      (node (ref "X2") (pin "10") (pinfunction "10_10") (pintype "passive"))
    )
    (net (code "29") (name "DCC5") (class "Default")
      (node (ref "B17") (pin "AC2") (pinfunction "AC2_AC2") (pintype "passive"))
      (node (ref "B18") (pin "AC2") (pinfunction "AC2_AC2") (pintype "passive"))
      (node (ref "B19") (pin "AC2") (pinfunction "AC2_AC2") (pintype "passive"))
      (node (ref "B20") (pin "AC2") (pinfunction "AC2_AC2") (pintype "passive"))
      (node (ref "C27") (pin "2") (pinfunction "2_2") (pintype "passive"))
      (node (ref "C28") (pin "2") (pinfunction "2_2") (pintype "passive"))
      (node (ref "C29") (pin "2") (pinfunction "2_2") (pintype "passive"))
      (node (ref "C30") (pin "2") (pinfunction "2_2") (pintype "passive"))
      (node (ref "OK5") (pin "2") (pinfunction "C_2") (pintype "passive"))
      (node (ref "OK5") (pin "4") (pinfunction "C_4") (pintype "passive"))
      (node (ref "OK5") (pin "6") (pinfunction "C_6") (pintype "passive"))
      (node (ref "OK5") (pin "8") (pinfunction "C_8") (pintype "passive"))
      (node (ref "X3") (pin "1") (pinfunction "1_1") (pintype "passive"))
    )
    (net (code "30") (name "DCC6") (class "Default")
      (node (ref "B21") (pin "AC2") (pinfunction "AC2_AC2") (pintype "passive"))
      (node (ref "B22") (pin "AC2") (pinfunction "AC2_AC2") (pintype "passive"))
      (node (ref "B23") (pin "AC2") (pinfunction "AC2_AC2") (pintype "passive"))
      (node (ref "B24") (pin "AC2") (pinfunction "AC2_AC2") (pintype "passive"))
      (node (ref "C31") (pin "2") (pinfunction "2_2") (pintype "passive"))
      (node (ref "C32") (pin "2") (pinfunction "2_2") (pintype "passive"))
      (node (ref "C33") (pin "2") (pinfunction "2_2") (pintype "passive"))
      (node (ref "C34") (pin "2") (pinfunction "2_2") (pintype "passive"))
      (node (ref "OK6") (pin "2") (pinfunction "C_2") (pintype "passive"))
      (node (ref "OK6") (pin "4") (pinfunction "C_4") (pintype "passive"))
      (node (ref "OK6") (pin "6") (pinfunction "C_6") (pintype "passive"))
      (node (ref "OK6") (pin "8") (pinfunction "C_8") (pintype "passive"))
      (node (ref "X3") (pin "10") (pinfunction "10_10") (pintype "passive"))
    )
    (net (code "31") (name "DCC7") (class "Default")
      (node (ref "B25") (pin "AC2") (pinfunction "AC2_AC2") (pintype "passive"))
      (node (ref "B26") (pin "AC2") (pinfunction "AC2_AC2") (pintype "passive"))
      (node (ref "B27") (pin "AC2") (pinfunction "AC2_AC2") (pintype "passive"))
      (node (ref "B28") (pin "AC2") (pinfunction "AC2_AC2") (pintype "passive"))
      (node (ref "C35") (pin "2") (pinfunction "2_2") (pintype "passive"))
      (node (ref "C36") (pin "2") (pinfunction "2_2") (pintype "passive"))
      (node (ref "C37") (pin "2") (pinfunction "2_2") (pintype "passive"))
      (node (ref "C38") (pin "2") (pinfunction "2_2") (pintype "passive"))
      (node (ref "OK7") (pin "2") (pinfunction "C_2") (pintype "passive"))
      (node (ref "OK7") (pin "4") (pinfunction "C_4") (pintype "passive"))
      (node (ref "OK7") (pin "6") (pinfunction "C_6") (pintype "passive"))
      (node (ref "OK7") (pin "8") (pinfunction "C_8") (pintype "passive"))
      (node (ref "X4") (pin "1") (pinfunction "1_1") (pintype "passive"))
    )
    (net (code "32") (name "DCC8") (class "Default")
      (node (ref "B29") (pin "AC2") (pinfunction "AC2_AC2") (pintype "passive"))
      (node (ref "B30") (pin "AC2") (pinfunction "AC2_AC2") (pintype "passive"))
      (node (ref "B31") (pin "AC2") (pinfunction "AC2_AC2") (pintype "passive"))
      (node (ref "B32") (pin "AC2") (pinfunction "AC2_AC2") (pintype "passive"))
      (node (ref "C39") (pin "2") (pinfunction "2_2") (pintype "passive"))
      (node (ref "C40") (pin "2") (pinfunction "2_2") (pintype "passive"))
      (node (ref "C41") (pin "2") (pinfunction "2_2") (pintype "passive"))
      (node (ref "C42") (pin "2") (pinfunction "2_2") (pintype "passive"))
      (node (ref "OK8") (pin "2") (pinfunction "C_2") (pintype "passive"))
      (node (ref "OK8") (pin "4") (pinfunction "C_4") (pintype "passive"))
      (node (ref "OK8") (pin "6") (pinfunction "C_6") (pintype "passive"))
      (node (ref "OK8") (pin "8") (pinfunction "C_8") (pintype "passive"))
      (node (ref "X4") (pin "10") (pinfunction "10_10") (pintype "passive"))
    )
    (net (code "33") (name "DTR") (class "Default")
      (node (ref "IC4") (pin "13") (pinfunction "PD7_13") (pintype "bidirectional"))
      (node (ref "R46") (pin "2") (pinfunction "2_2") (pintype "passive"))
    )
    (net (code "34") (name "E2") (class "Default")
      (node (ref "IC1") (pin "4") (pinfunction "(XCK0/AIN0)_PE2_4") (pintype "bidirectional"))
      (node (ref "T22") (pin "C") (pinfunction "C_C") (pintype "passive"))
    )
    (net (code "35") (name "E3") (class "Default")
      (node (ref "IC1") (pin "5") (pinfunction "(OC3A/AIN1)_PE3_5") (pintype "bidirectional"))
      (node (ref "T21") (pin "C") (pinfunction "C_C") (pintype "passive"))
    )
    (net (code "36") (name "E4") (class "Default")
      (node (ref "IC1") (pin "6") (pinfunction "(OC3B/INT4)_PE4_6") (pintype "bidirectional"))
      (node (ref "OK6") (pin "10") (pinfunction "COL_10") (pintype "passive"))
    )
    (net (code "37") (name "E5") (class "Default")
      (node (ref "IC1") (pin "7") (pinfunction "(OC3C/INT5)_PE5_7") (pintype "bidirectional"))
      (node (ref "OK6") (pin "12") (pinfunction "COL_12") (pintype "passive"))
    )
    (net (code "38") (name "E6") (class "Default")
      (node (ref "IC1") (pin "8") (pinfunction "(T3/INT6)_PE6_8") (pintype "bidirectional"))
      (node (ref "OK6") (pin "14") (pinfunction "COL_14") (pintype "passive"))
    )
    (net (code "39") (name "E7") (class "Default")
      (node (ref "IC1") (pin "9") (pinfunction "(CLKO/ICP3/INT7)_PE7_9") (pintype "bidirectional"))
      (node (ref "OK6") (pin "16") (pinfunction "COL_16") (pintype "passive"))
    )
    (net (code "40") (name "F0") (class "Default")
      (node (ref "IC1") (pin "97") (pinfunction "PF0_(ADC0)_97") (pintype "bidirectional"))
      (node (ref "T25") (pin "C") (pinfunction "C_C") (pintype "passive"))
    )
    (net (code "41") (name "F1") (class "Default")
      (node (ref "IC1") (pin "96") (pinfunction "PF1_(ADC1)_96") (pintype "bidirectional"))
      (node (ref "T26") (pin "C") (pinfunction "C_C") (pintype "passive"))
    )
    (net (code "42") (name "F2") (class "Default")
      (node (ref "IC1") (pin "95") (pinfunction "PF2_(ADC2)_95") (pintype "bidirectional"))
      (node (ref "T27") (pin "C") (pinfunction "C_C") (pintype "passive"))
    )
    (net (code "43") (name "F3") (class "Default")
      (node (ref "IC1") (pin "94") (pinfunction "PF3_(ADC3)_94") (pintype "bidirectional"))
      (node (ref "T28") (pin "C") (pinfunction "C_C") (pintype "passive"))
    )
    (net (code "44") (name "F4") (class "Default")
      (node (ref "IC1") (pin "93") (pinfunction "PF4_(ADC4/TCK)_93") (pintype "bidirectional"))
      (node (ref "OK7") (pin "16") (pinfunction "COL_16") (pintype "passive"))
    )
    (net (code "45") (name "F5") (class "Default")
      (node (ref "IC1") (pin "92") (pinfunction "PF5_(ADC5/TMS)_92") (pintype "bidirectional"))
      (node (ref "OK7") (pin "14") (pinfunction "COL_14") (pintype "passive"))
    )
    (net (code "46") (name "F6") (class "Default")
      (node (ref "IC1") (pin "91") (pinfunction "PF6_(ADC6/TDO)_91") (pintype "bidirectional"))
      (node (ref "OK7") (pin "12") (pinfunction "COL_12") (pintype "passive"))
    )
    (net (code "47") (name "F7") (class "Default")
      (node (ref "IC1") (pin "90") (pinfunction "PF7_(ADC7/TDI)_90") (pintype "bidirectional"))
      (node (ref "OK7") (pin "10") (pinfunction "COL_10") (pintype "passive"))
    )
    (net (code "48") (name "GND") (class "Default")
      (node (ref "C1") (pin "2") (pinfunction "2_2") (pintype "passive"))
      (node (ref "C10") (pin "2") (pinfunction "2_2") (pintype "passive"))
      (node (ref "C2") (pin "2") (pinfunction "2_2") (pintype "passive"))
      (node (ref "C3") (pin "2") (pinfunction "2_2") (pintype "passive"))
      (node (ref "C4") (pin "2") (pinfunction "2_2") (pintype "passive"))
      (node (ref "C5") (pin "2") (pinfunction "2_2") (pintype "passive"))
      (node (ref "C6") (pin "2") (pinfunction "2_2") (pintype "passive"))
      (node (ref "C7") (pin "2") (pinfunction "2_2") (pintype "passive"))
      (node (ref "C8") (pin "2") (pinfunction "2_2") (pintype "passive"))
      (node (ref "C9") (pin "-") (pinfunction "-_-") (pintype "passive"))
      (node (ref "IC1") (pin "11") (pinfunction "GND_2_11") (pintype "passive"))
      (node (ref "IC1") (pin "32") (pinfunction "GND_4_32") (pintype "passive"))
      (node (ref "IC1") (pin "62") (pinfunction "GND_3_62") (pintype "passive"))
      (node (ref "IC1") (pin "81") (pinfunction "GND_5_81") (pintype "passive"))
      (node (ref "IC1") (pin "99") (pinfunction "GND_99") (pintype "passive"))
      (node (ref "IC2") (pin "2") (pinfunction "VSS_2") (pintype "passive"))
      (node (ref "IC2") (pin "8") (pinfunction "RS_8") (pintype "input"))
      (node (ref "IC3") (pin "9") (pinfunction "VSS_9") (pintype "power_in"))
      (node (ref "IC5") (pin "4") (pinfunction "GND1_4") (pintype "passive"))
      (node (ref "IC8") (pin "3") (pinfunction "GND_3") (pintype "passive"))
      (node (ref "ISP") (pin "6") (pinfunction "S_6") (pintype "passive"))
      (node (ref "I²C") (pin "3") (pinfunction "S_3") (pintype "passive"))
      (node (ref "J1") (pin "3") (pinfunction "3_3") (pintype "passive"))
      (node (ref "J1") (pin "4") (pinfunction "4_4") (pintype "passive"))
      (node (ref "J1") (pin "SHELL") (pinfunction "SHIELD_SHELL") (pintype "passive"))
      (node (ref "J1") (pin "SHELL1") (pinfunction "SHIELD_SHELL1") (pintype "passive"))
      (node (ref "J2") (pin "3") (pinfunction "3_3") (pintype "passive"))
      (node (ref "J2") (pin "4") (pinfunction "4_4") (pintype "passive"))
      (node (ref "J2") (pin "SHELL") (pinfunction "SHIELD_SHELL") (pintype "passive"))
      (node (ref "J2") (pin "SHELL1") (pinfunction "SHIELD_SHELL1") (pintype "passive"))
      (node (ref "OK1") (pin "11") (pinfunction "EMIT_11") (pintype "passive"))
      (node (ref "OK1") (pin "13") (pinfunction "EMIT_13") (pintype "passive"))
      (node (ref "OK1") (pin "15") (pinfunction "EMIT_15") (pintype "passive"))
      (node (ref "OK1") (pin "9") (pinfunction "EMIT_9") (pintype "passive"))
      (node (ref "OK2") (pin "11") (pinfunction "EMIT_11") (pintype "passive"))
      (node (ref "OK2") (pin "13") (pinfunction "EMIT_13") (pintype "passive"))
      (node (ref "OK2") (pin "15") (pinfunction "EMIT_15") (pintype "passive"))
      (node (ref "OK2") (pin "9") (pinfunction "EMIT_9") (pintype "passive"))
      (node (ref "OK3") (pin "11") (pinfunction "EMIT_11") (pintype "passive"))
      (node (ref "OK3") (pin "13") (pinfunction "EMIT_13") (pintype "passive"))
      (node (ref "OK3") (pin "15") (pinfunction "EMIT_15") (pintype "passive"))
      (node (ref "OK3") (pin "9") (pinfunction "EMIT_9") (pintype "passive"))
      (node (ref "OK4") (pin "11") (pinfunction "EMIT_11") (pintype "passive"))
      (node (ref "OK4") (pin "13") (pinfunction "EMIT_13") (pintype "passive"))
      (node (ref "OK4") (pin "15") (pinfunction "EMIT_15") (pintype "passive"))
      (node (ref "OK4") (pin "9") (pinfunction "EMIT_9") (pintype "passive"))
      (node (ref "OK5") (pin "11") (pinfunction "EMIT_11") (pintype "passive"))
      (node (ref "OK5") (pin "13") (pinfunction "EMIT_13") (pintype "passive"))
      (node (ref "OK5") (pin "15") (pinfunction "EMIT_15") (pintype "passive"))
      (node (ref "OK5") (pin "9") (pinfunction "EMIT_9") (pintype "passive"))
      (node (ref "OK6") (pin "11") (pinfunction "EMIT_11") (pintype "passive"))
      (node (ref "OK6") (pin "13") (pinfunction "EMIT_13") (pintype "passive"))
      (node (ref "OK6") (pin "15") (pinfunction "EMIT_15") (pintype "passive"))
      (node (ref "OK6") (pin "9") (pinfunction "EMIT_9") (pintype "passive"))
      (node (ref "OK7") (pin "11") (pinfunction "EMIT_11") (pintype "passive"))
      (node (ref "OK7") (pin "13") (pinfunction "EMIT_13") (pintype "passive"))
      (node (ref "OK7") (pin "15") (pinfunction "EMIT_15") (pintype "passive"))
      (node (ref "OK7") (pin "9") (pinfunction "EMIT_9") (pintype "passive"))
      (node (ref "OK8") (pin "11") (pinfunction "EMIT_11") (pintype "passive"))
      (node (ref "OK8") (pin "13") (pinfunction "EMIT_13") (pintype "passive"))
      (node (ref "OK8") (pin "15") (pinfunction "EMIT_15") (pintype "passive"))
      (node (ref "OK8") (pin "9") (pinfunction "EMIT_9") (pintype "passive"))
      (node (ref "OK9") (pin "3") (pinfunction "EMIT_3") (pintype "passive"))
      (node (ref "R4") (pin "2") (pinfunction "2_2") (pintype "passive"))
      (node (ref "R5") (pin "2") (pinfunction "2_2") (pintype "passive"))
      (node (ref "S1") (pin "1") (pinfunction "1_1") (pintype "passive"))
      (node (ref "S1") (pin "2") (pinfunction "2_2") (pintype "passive"))
      (node (ref "S1") (pin "3") (pinfunction "3_3") (pintype "passive"))
      (node (ref "S1") (pin "4") (pinfunction "4_4") (pintype "passive"))
      (node (ref "U$15") (pin "P$1") (pinfunction "P$1_P$1") (pintype "bidirectional"))
      (node (ref "U$15") (pin "P$2") (pinfunction "P$2_P$2") (pintype "bidirectional"))
      (node (ref "X17") (pin "1") (pinfunction "1_1") (pintype "passive"))
      (node (ref "X5") (pin "1") (pinfunction "1_1") (pintype "passive"))
      (node (ref "X7") (pin "1") (pinfunction "1_1") (pintype "passive"))
    )
    (net (code "49") (name "GND2") (class "Default")
      (node (ref "C43") (pin "2") (pinfunction "2_2") (pintype "passive"))
      (node (ref "C44") (pin "2") (pinfunction "2_2") (pintype "passive"))
      (node (ref "C45") (pin "2") (pinfunction "2_2") (pintype "passive"))
      (node (ref "C47") (pin "2") (pinfunction "2_2") (pintype "passive"))
      (node (ref "GND") (pin "TP") (pinfunction "TP_TP") (pintype "input"))
      (node (ref "IC4") (pin "28") (pinfunction "UGND_28") (pintype "power_in"))
      (node (ref "IC4") (pin "3") (pinfunction "GND_3") (pintype "power_in"))
      (node (ref "IC4") (pin "33") (pinfunction "EXP_33") (pintype "power_in"))
      (node (ref "IC5") (pin "5") (pinfunction "GND2_5") (pintype "passive"))
      (node (ref "X6") (pin "5") (pinfunction "5_5") (pintype "passive"))
    )
    (net (code "50") (name "H0") (class "Default")
      (node (ref "IC1") (pin "12") (pinfunction "(RXD2)_PH0_12") (pintype "bidirectional"))
      (node (ref "T20") (pin "C") (pinfunction "C_C") (pintype "passive"))
    )
    (net (code "51") (name "H1") (class "Default")
      (node (ref "IC1") (pin "13") (pinfunction "(TXD2)_PH1_13") (pintype "bidirectional"))
      (node (ref "T19") (pin "C") (pinfunction "C_C") (pintype "passive"))
    )
    (net (code "52") (name "H2") (class "Default")
      (node (ref "IC1") (pin "14") (pinfunction "(XCK2)_PH2_14") (pintype "bidirectional"))
      (node (ref "T18") (pin "C") (pinfunction "C_C") (pintype "passive"))
    )
    (net (code "53") (name "H3") (class "Default")
      (node (ref "IC1") (pin "15") (pinfunction "(OC4A)_PH3_15") (pintype "bidirectional"))
      (node (ref "T17") (pin "C") (pinfunction "C_C") (pintype "passive"))
    )
    (net (code "54") (name "H4") (class "Default")
      (node (ref "IC1") (pin "16") (pinfunction "(OC4B)_PH4_16") (pintype "bidirectional"))
      (node (ref "OK5") (pin "16") (pinfunction "COL_16") (pintype "passive"))
    )
    (net (code "55") (name "H5") (class "Default")
      (node (ref "IC1") (pin "17") (pinfunction "(OC4C)_PH5_17") (pintype "bidirectional"))
      (node (ref "OK5") (pin "14") (pinfunction "COL_14") (pintype "passive"))
    )
    (net (code "56") (name "H6") (class "Default")
      (node (ref "IC1") (pin "18") (pinfunction "(OC2B)_PH6_18") (pintype "bidirectional"))
      (node (ref "OK5") (pin "12") (pinfunction "COL_12") (pintype "passive"))
    )
    (net (code "57") (name "H7") (class "Default")
      (node (ref "IC1") (pin "27") (pinfunction "(T4)_PH7_27") (pintype "bidirectional"))
      (node (ref "OK5") (pin "10") (pinfunction "COL_10") (pintype "passive"))
    )
    (net (code "58") (name "INT") (class "Default")
      (node (ref "IC1") (pin "45") (pinfunction "(RXD1/INT2)_PD2_45") (pintype "bidirectional"))
      (node (ref "IC3") (pin "12") (pinfunction "~{INT}_12") (pintype "output"))
    )
    (net (code "59") (name "J0") (class "Default")
      (node (ref "IC1") (pin "63") (pinfunction "PJ0_(RXD3/PCINT9)_63") (pintype "bidirectional"))
      (node (ref "T8") (pin "C") (pinfunction "C_C") (pintype "passive"))
    )
    (net (code "60") (name "J1") (class "Default")
      (node (ref "IC1") (pin "64") (pinfunction "PJ1_(TXD3/PCINT10)_64") (pintype "bidirectional"))
      (node (ref "T7") (pin "C") (pinfunction "C_C") (pintype "passive"))
    )
    (net (code "61") (name "J2") (class "Default")
      (node (ref "IC1") (pin "65") (pinfunction "PJ2_(XCK3/PCINT11)_65") (pintype "bidirectional"))
      (node (ref "T6") (pin "C") (pinfunction "C_C") (pintype "passive"))
    )
    (net (code "62") (name "J3") (class "Default")
      (node (ref "IC1") (pin "66") (pinfunction "PJ3_(PCINT12)_66") (pintype "bidirectional"))
      (node (ref "T5") (pin "C") (pinfunction "C_C") (pintype "passive"))
    )
    (net (code "63") (name "J4") (class "Default")
      (node (ref "IC1") (pin "67") (pinfunction "PJ4_(PCINT13)_67") (pintype "bidirectional"))
      (node (ref "OK2") (pin "10") (pinfunction "COL_10") (pintype "passive"))
    )
    (net (code "64") (name "J5") (class "Default")
      (node (ref "IC1") (pin "68") (pinfunction "PJ5_(PCINT14)_68") (pintype "bidirectional"))
      (node (ref "OK2") (pin "12") (pinfunction "COL_12") (pintype "passive"))
    )
    (net (code "65") (name "J6") (class "Default")
      (node (ref "IC1") (pin "69") (pinfunction "PJ6_(PCINT15)_69") (pintype "bidirectional"))
      (node (ref "OK2") (pin "14") (pinfunction "COL_14") (pintype "passive"))
    )
    (net (code "66") (name "J7") (class "Default")
      (node (ref "IC1") (pin "79") (pinfunction "PJ7_79") (pintype "bidirectional"))
      (node (ref "OK2") (pin "16") (pinfunction "COL_16") (pintype "passive"))
    )
    (net (code "67") (name "K0") (class "Default")
      (node (ref "IC1") (pin "89") (pinfunction "PK0_(ADC8/PCINT16)_89") (pintype "bidirectional"))
      (node (ref "T29") (pin "C") (pinfunction "C_C") (pintype "passive"))
    )
    (net (code "68") (name "K1") (class "Default")
      (node (ref "IC1") (pin "88") (pinfunction "PK1_(ADC9/PCINT17)_88") (pintype "bidirectional"))
      (node (ref "T30") (pin "C") (pinfunction "C_C") (pintype "passive"))
    )
    (net (code "69") (name "K2") (class "Default")
      (node (ref "IC1") (pin "87") (pinfunction "PK2_(ADC10/PCINT18)_87") (pintype "bidirectional"))
      (node (ref "T31") (pin "C") (pinfunction "C_C") (pintype "passive"))
    )
    (net (code "70") (name "K3") (class "Default")
      (node (ref "IC1") (pin "86") (pinfunction "PK3_(ADC11/PCINT19)_86") (pintype "bidirectional"))
      (node (ref "T32") (pin "C") (pinfunction "C_C") (pintype "passive"))
    )
    (net (code "71") (name "K4") (class "Default")
      (node (ref "IC1") (pin "85") (pinfunction "PK4_(ADC12/PCINT20)_85") (pintype "bidirectional"))
      (node (ref "OK8") (pin "10") (pinfunction "COL_10") (pintype "passive"))
    )
    (net (code "72") (name "K5") (class "Default")
      (node (ref "IC1") (pin "84") (pinfunction "PK5_(ADC13/PCINT21)_84") (pintype "bidirectional"))
      (node (ref "OK8") (pin "12") (pinfunction "COL_12") (pintype "passive"))
    )
    (net (code "73") (name "K6") (class "Default")
      (node (ref "IC1") (pin "83") (pinfunction "PK6_(ADC14/PCINT22)_83") (pintype "bidirectional"))
      (node (ref "OK8") (pin "14") (pinfunction "COL_14") (pintype "passive"))
    )
    (net (code "74") (name "K7") (class "Default")
      (node (ref "IC1") (pin "82") (pinfunction "PK7_(ADC15/PCINT23)_82") (pintype "bidirectional"))
      (node (ref "OK8") (pin "16") (pinfunction "COL_16") (pintype "passive"))
    )
    (net (code "75") (name "L0") (class "Default")
      (node (ref "IC1") (pin "35") (pinfunction "(ICP4)_PL0_35") (pintype "bidirectional"))
      (node (ref "OK4") (pin "16") (pinfunction "COL_16") (pintype "passive"))
    )
    (net (code "76") (name "L1") (class "Default")
      (node (ref "IC1") (pin "36") (pinfunction "(ICP5)_PL1_36") (pintype "bidirectional"))
      (node (ref "OK4") (pin "14") (pinfunction "COL_14") (pintype "passive"))
    )
    (net (code "77") (name "L2") (class "Default")
      (node (ref "IC1") (pin "37") (pinfunction "(T5)_PL2_37") (pintype "bidirectional"))
      (node (ref "OK4") (pin "12") (pinfunction "COL_12") (pintype "passive"))
    )
    (net (code "78") (name "L3") (class "Default")
      (node (ref "IC1") (pin "38") (pinfunction "(OC5A)_PL3_38") (pintype "bidirectional"))
      (node (ref "OK4") (pin "10") (pinfunction "COL_10") (pintype "passive"))
    )
    (net (code "79") (name "L4") (class "Default")
      (node (ref "IC1") (pin "39") (pinfunction "(OC5B)_PL4_39") (pintype "bidirectional"))
      (node (ref "T16") (pin "C") (pinfunction "C_C") (pintype "passive"))
    )
    (net (code "80") (name "L5") (class "Default")
      (node (ref "IC1") (pin "40") (pinfunction "OC5C)_PL5_40") (pintype "bidirectional"))
      (node (ref "T15") (pin "C") (pinfunction "C_C") (pintype "passive"))
    )
    (net (code "81") (name "L6") (class "Default")
      (node (ref "IC1") (pin "41") (pinfunction "PL6_41") (pintype "bidirectional"))
      (node (ref "T14") (pin "C") (pinfunction "C_C") (pintype "passive"))
    )
    (net (code "82") (name "L7") (class "Default")
      (node (ref "IC1") (pin "42") (pinfunction "PL7_42") (pintype "bidirectional"))
      (node (ref "T13") (pin "C") (pinfunction "C_C") (pintype "passive"))
    )
    (net (code "83") (name "MISO") (class "Default")
      (node (ref "IC1") (pin "22") (pinfunction "(MISO/PCINT3)_PB3_22") (pintype "bidirectional"))
      (node (ref "IC3") (pin "15") (pinfunction "SO_15") (pintype "output"))
      (node (ref "ISP") (pin "1") (pinfunction "S_1") (pintype "passive"))
    )
    (net (code "84") (name "MISO2") (class "Default")
      (node (ref "IC4") (pin "17") (pinfunction "PB3_17") (pintype "bidirectional"))
      (node (ref "MISO") (pin "TP") (pinfunction "TP_TP") (pintype "input"))
    )
    (net (code "85") (name "MOSI") (class "Default")
      (node (ref "IC1") (pin "21") (pinfunction "(MOSI/PCINT2)_PB2_21") (pintype "bidirectional"))
      (node (ref "IC3") (pin "14") (pinfunction "SI_14") (pintype "input"))
      (node (ref "ISP") (pin "4") (pinfunction "S_4") (pintype "passive"))
    )
    (net (code "86") (name "MOSI2") (class "Default")
      (node (ref "IC4") (pin "16") (pinfunction "PB2_16") (pintype "bidirectional"))
      (node (ref "MOSI") (pin "TP") (pinfunction "TP_TP") (pintype "input"))
    )
    (net (code "87") (name "Net-(B1-Pad+)") (class "Default")
      (node (ref "B1") (pin "+") (pinfunction "+_+") (pintype "passive"))
      (node (ref "B1") (pin "-") (pinfunction "-_-") (pintype "passive"))
    )
    (net (code "88") (name "Net-(B1-PadAC1)") (class "Default")
      (node (ref "B1") (pin "AC1") (pinfunction "AC1_AC1") (pintype "passive"))
      (node (ref "R9") (pin "2") (pinfunction "2_2") (pintype "passive"))
      (node (ref "X1") (pin "2") (pinfunction "2_2") (pintype "passive"))
    )
    (net (code "89") (name "Net-(B2-Pad+)") (class "Default")
      (node (ref "B2") (pin "+") (pinfunction "+_+") (pintype "passive"))
      (node (ref "B2") (pin "-") (pinfunction "-_-") (pintype "passive"))
    )
    (net (code "90") (name "Net-(B2-PadAC1)") (class "Default")
      (node (ref "B2") (pin "AC1") (pinfunction "AC1_AC1") (pintype "passive"))
      (node (ref "R10") (pin "2") (pinfunction "2_2") (pintype "passive"))
      (node (ref "X1") (pin "3") (pinfunction "3_3") (pintype "passive"))
    )
    (net (code "91") (name "Net-(B3-Pad+)") (class "Default")
      (node (ref "B3") (pin "+") (pinfunction "+_+") (pintype "passive"))
      (node (ref "B3") (pin "-") (pinfunction "-_-") (pintype "passive"))
    )
    (net (code "92") (name "Net-(B3-PadAC1)") (class "Default")
      (node (ref "B3") (pin "AC1") (pinfunction "AC1_AC1") (pintype "passive"))
      (node (ref "R11") (pin "2") (pinfunction "2_2") (pintype "passive"))
      (node (ref "X1") (pin "4") (pinfunction "4_4") (pintype "passive"))
    )
    (net (code "93") (name "Net-(B4-Pad+)") (class "Default")
      (node (ref "B4") (pin "+") (pinfunction "+_+") (pintype "passive"))
      (node (ref "B4") (pin "-") (pinfunction "-_-") (pintype "passive"))
    )
    (net (code "94") (name "Net-(B4-PadAC1)") (class "Default")
      (node (ref "B4") (pin "AC1") (pinfunction "AC1_AC1") (pintype "passive"))
      (node (ref "R12") (pin "2") (pinfunction "2_2") (pintype "passive"))
      (node (ref "X1") (pin "5") (pinfunction "5_5") (pintype "passive"))
    )
    (net (code "95") (name "Net-(B5-Pad+)") (class "Default")
      (node (ref "B5") (pin "+") (pinfunction "+_+") (pintype "passive"))
      (node (ref "B5") (pin "-") (pinfunction "-_-") (pintype "passive"))
    )
    (net (code "96") (name "Net-(B5-PadAC1)") (class "Default")
      (node (ref "B5") (pin "AC1") (pinfunction "AC1_AC1") (pintype "passive"))
      (node (ref "R13") (pin "2") (pinfunction "2_2") (pintype "passive"))
      (node (ref "X1") (pin "6") (pinfunction "6_6") (pintype "passive"))
    )
    (net (code "97") (name "Net-(B6-Pad+)") (class "Default")
      (node (ref "B6") (pin "+") (pinfunction "+_+") (pintype "passive"))
      (node (ref "B6") (pin "-") (pinfunction "-_-") (pintype "passive"))
    )
    (net (code "98") (name "Net-(B6-PadAC1)") (class "Default")
      (node (ref "B6") (pin "AC1") (pinfunction "AC1_AC1") (pintype "passive"))
      (node (ref "R14") (pin "2") (pinfunction "2_2") (pintype "passive"))
      (node (ref "X1") (pin "7") (pinfunction "7_7") (pintype "passive"))
    )
    (net (code "99") (name "Net-(B7-Pad+)") (class "Default")
      (node (ref "B7") (pin "+") (pinfunction "+_+") (pintype "passive"))
      (node (ref "B7") (pin "-") (pinfunction "-_-") (pintype "passive"))
    )
    (net (code "100") (name "Net-(B7-PadAC1)") (class "Default")
      (node (ref "B7") (pin "AC1") (pinfunction "AC1_AC1") (pintype "passive"))
      (node (ref "R15") (pin "2") (pinfunction "2_2") (pintype "passive"))
      (node (ref "X1") (pin "8") (pinfunction "8_8") (pintype "passive"))
    )
    (net (code "101") (name "Net-(B8-Pad+)") (class "Default")
      (node (ref "B8") (pin "+") (pinfunction "+_+") (pintype "passive"))
      (node (ref "B8") (pin "-") (pinfunction "-_-") (pintype "passive"))
    )
    (net (code "102") (name "Net-(B8-PadAC1)") (class "Default")
      (node (ref "B8") (pin "AC1") (pinfunction "AC1_AC1") (pintype "passive"))
      (node (ref "R16") (pin "2") (pinfunction "2_2") (pintype "passive"))
      (node (ref "X1") (pin "9") (pinfunction "9_9") (pintype "passive"))
    )
    (net (code "103") (name "Net-(B9-Pad+)") (class "Default")
      (node (ref "B9") (pin "+") (pinfunction "+_+") (pintype "passive"))
      (node (ref "B9") (pin "-") (pinfunction "-_-") (pintype "passive"))
    )
    (net (code "104") (name "Net-(B9-PadAC1)") (class "Default")
      (node (ref "B9") (pin "AC1") (pinfunction "AC1_AC1") (pintype "passive"))
      (node (ref "R17") (pin "2") (pinfunction "2_2") (pintype "passive"))
      (node (ref "X2") (pin "2") (pinfunction "2_2") (pintype "passive"))
    )
    (net (code "105") (name "Net-(B10-Pad+)") (class "Default")
      (node (ref "B10") (pin "+") (pinfunction "+_+") (pintype "passive"))
      (node (ref "B10") (pin "-") (pinfunction "-_-") (pintype "passive"))
    )
    (net (code "106") (name "Net-(B10-PadAC1)") (class "Default")
      (node (ref "B10") (pin "AC1") (pinfunction "AC1_AC1") (pintype "passive"))
      (node (ref "R18") (pin "2") (pinfunction "2_2") (pintype "passive"))
      (node (ref "X2") (pin "3") (pinfunction "3_3") (pintype "passive"))
    )
    (net (code "107") (name "Net-(B11-Pad+)") (class "Default")
      (node (ref "B11") (pin "+") (pinfunction "+_+") (pintype "passive"))
      (node (ref "B11") (pin "-") (pinfunction "-_-") (pintype "passive"))
    )
    (net (code "108") (name "Net-(B11-PadAC1)") (class "Default")
      (node (ref "B11") (pin "AC1") (pinfunction "AC1_AC1") (pintype "passive"))
      (node (ref "R19") (pin "2") (pinfunction "2_2") (pintype "passive"))
      (node (ref "X2") (pin "4") (pinfunction "4_4") (pintype "passive"))
    )
    (net (code "109") (name "Net-(B12-Pad+)") (class "Default")
      (node (ref "B12") (pin "+") (pinfunction "+_+") (pintype "passive"))
      (node (ref "B12") (pin "-") (pinfunction "-_-") (pintype "passive"))
    )
    (net (code "110") (name "Net-(B12-PadAC1)") (class "Default")
      (node (ref "B12") (pin "AC1") (pinfunction "AC1_AC1") (pintype "passive"))
      (node (ref "R20") (pin "2") (pinfunction "2_2") (pintype "passive"))
      (node (ref "X2") (pin "5") (pinfunction "5_5") (pintype "passive"))
    )
    (net (code "111") (name "Net-(B13-Pad+)") (class "Default")
      (node (ref "B13") (pin "+") (pinfunction "+_+") (pintype "passive"))
      (node (ref "B13") (pin "-") (pinfunction "-_-") (pintype "passive"))
    )
    (net (code "112") (name "Net-(B13-PadAC1)") (class "Default")
      (node (ref "B13") (pin "AC1") (pinfunction "AC1_AC1") (pintype "passive"))
      (node (ref "R21") (pin "2") (pinfunction "2_2") (pintype "passive"))
      (node (ref "X2") (pin "6") (pinfunction "6_6") (pintype "passive"))
    )
    (net (code "113") (name "Net-(B14-Pad+)") (class "Default")
      (node (ref "B14") (pin "+") (pinfunction "+_+") (pintype "passive"))
      (node (ref "B14") (pin "-") (pinfunction "-_-") (pintype "passive"))
    )
    (net (code "114") (name "Net-(B14-PadAC1)") (class "Default")
      (node (ref "B14") (pin "AC1") (pinfunction "AC1_AC1") (pintype "passive"))
      (node (ref "R22") (pin "2") (pinfunction "2_2") (pintype "passive"))
      (node (ref "X2") (pin "7") (pinfunction "7_7") (pintype "passive"))
    )
    (net (code "115") (name "Net-(B15-Pad+)") (class "Default")
      (node (ref "B15") (pin "+") (pinfunction "+_+") (pintype "passive"))
      (node (ref "B15") (pin "-") (pinfunction "-_-") (pintype "passive"))
    )
    (net (code "116") (name "Net-(B15-PadAC1)") (class "Default")
      (node (ref "B15") (pin "AC1") (pinfunction "AC1_AC1") (pintype "passive"))
      (node (ref "R23") (pin "2") (pinfunction "2_2") (pintype "passive"))
      (node (ref "X2") (pin "8") (pinfunction "8_8") (pintype "passive"))
    )
    (net (code "117") (name "Net-(B16-Pad+)") (class "Default")
      (node (ref "B16") (pin "+") (pinfunction "+_+") (pintype "passive"))
      (node (ref "B16") (pin "-") (pinfunction "-_-") (pintype "passive"))
    )
    (net (code "118") (name "Net-(B16-PadAC1)") (class "Default")
      (node (ref "B16") (pin "AC1") (pinfunction "AC1_AC1") (pintype "passive"))
      (node (ref "R24") (pin "2") (pinfunction "2_2") (pintype "passive"))
      (node (ref "X2") (pin "9") (pinfunction "9_9") (pintype "passive"))
    )
    (net (code "119") (name "Net-(B17-Pad+)") (class "Default")
      (node (ref "B17") (pin "+") (pinfunction "+_+") (pintype "passive"))
      (node (ref "B17") (pin "-") (pinfunction "-_-") (pintype "passive"))
    )
    (net (code "120") (name "Net-(B17-PadAC1)") (class "Default")
      (node (ref "B17") (pin "AC1") (pinfunction "AC1_AC1") (pintype "passive"))
      (node (ref "R25") (pin "2") (pinfunction "2_2") (pintype "passive"))
      (node (ref "X3") (pin "2") (pinfunction "2_2") (pintype "passive"))
    )
    (net (code "121") (name "Net-(B18-Pad+)") (class "Default")
      (node (ref "B18") (pin "+") (pinfunction "+_+") (pintype "passive"))
      (node (ref "B18") (pin "-") (pinfunction "-_-") (pintype "passive"))
    )
    (net (code "122") (name "Net-(B18-PadAC1)") (class "Default")
      (node (ref "B18") (pin "AC1") (pinfunction "AC1_AC1") (pintype "passive"))
      (node (ref "R26") (pin "2") (pinfunction "2_2") (pintype "passive"))
      (node (ref "X3") (pin "3") (pinfunction "3_3") (pintype "passive"))
    )
    (net (code "123") (name "Net-(B19-Pad+)") (class "Default")
      (node (ref "B19") (pin "+") (pinfunction "+_+") (pintype "passive"))
      (node (ref "B19") (pin "-") (pinfunction "-_-") (pintype "passive"))
    )
    (net (code "124") (name "Net-(B19-PadAC1)") (class "Default")
      (node (ref "B19") (pin "AC1") (pinfunction "AC1_AC1") (pintype "passive"))
      (node (ref "R27") (pin "2") (pinfunction "2_2") (pintype "passive"))
      (node (ref "X3") (pin "4") (pinfunction "4_4") (pintype "passive"))
    )
    (net (code "125") (name "Net-(B20-Pad+)") (class "Default")
      (node (ref "B20") (pin "+") (pinfunction "+_+") (pintype "passive"))
      (node (ref "B20") (pin "-") (pinfunction "-_-") (pintype "passive"))
    )
    (net (code "126") (name "Net-(B20-PadAC1)") (class "Default")
      (node (ref "B20") (pin "AC1") (pinfunction "AC1_AC1") (pintype "passive"))
      (node (ref "R28") (pin "2") (pinfunction "2_2") (pintype "passive"))
      (node (ref "X3") (pin "5") (pinfunction "5_5") (pintype "passive"))
    )
    (net (code "127") (name "Net-(B21-Pad+)") (class "Default")
      (node (ref "B21") (pin "+") (pinfunction "+_+") (pintype "passive"))
      (node (ref "B21") (pin "-") (pinfunction "-_-") (pintype "passive"))
    )
    (net (code "128") (name "Net-(B21-PadAC1)") (class "Default")
      (node (ref "B21") (pin "AC1") (pinfunction "AC1_AC1") (pintype "passive"))
      (node (ref "R29") (pin "2") (pinfunction "2_2") (pintype "passive"))
      (node (ref "X3") (pin "6") (pinfunction "6_6") (pintype "passive"))
    )
    (net (code "129") (name "Net-(B22-Pad+)") (class "Default")
      (node (ref "B22") (pin "+") (pinfunction "+_+") (pintype "passive"))
      (node (ref "B22") (pin "-") (pinfunction "-_-") (pintype "passive"))
    )
    (net (code "130") (name "Net-(B22-PadAC1)") (class "Default")
      (node (ref "B22") (pin "AC1") (pinfunction "AC1_AC1") (pintype "passive"))
      (node (ref "R30") (pin "2") (pinfunction "2_2") (pintype "passive"))
      (node (ref "X3") (pin "7") (pinfunction "7_7") (pintype "passive"))
    )
    (net (code "131") (name "Net-(B23-Pad+)") (class "Default")
      (node (ref "B23") (pin "+") (pinfunction "+_+") (pintype "passive"))
      (node (ref "B23") (pin "-") (pinfunction "-_-") (pintype "passive"))
    )
    (net (code "132") (name "Net-(B23-PadAC1)") (class "Default")
      (node (ref "B23") (pin "AC1") (pinfunction "AC1_AC1") (pintype "passive"))
      (node (ref "R31") (pin "2") (pinfunction "2_2") (pintype "passive"))
      (node (ref "X3") (pin "8") (pinfunction "8_8") (pintype "passive"))
    )
    (net (code "133") (name "Net-(B24-Pad+)") (class "Default")
      (node (ref "B24") (pin "+") (pinfunction "+_+") (pintype "passive"))
      (node (ref "B24") (pin "-") (pinfunction "-_-") (pintype "passive"))
    )
    (net (code "134") (name "Net-(B24-PadAC1)") (class "Default")
      (node (ref "B24") (pin "AC1") (pinfunction "AC1_AC1") (pintype "passive"))
      (node (ref "R32") (pin "2") (pinfunction "2_2") (pintype "passive"))
      (node (ref "X3") (pin "9") (pinfunction "9_9") (pintype "passive"))
    )
    (net (code "135") (name "Net-(B25-Pad+)") (class "Default")
      (node (ref "B25") (pin "+") (pinfunction "+_+") (pintype "passive"))
      (node (ref "B25") (pin "-") (pinfunction "-_-") (pintype "passive"))
    )
    (net (code "136") (name "Net-(B25-PadAC1)") (class "Default")
      (node (ref "B25") (pin "AC1") (pinfunction "AC1_AC1") (pintype "passive"))
      (node (ref "R33") (pin "2") (pinfunction "2_2") (pintype "passive"))
      (node (ref "X4") (pin "2") (pinfunction "2_2") (pintype "passive"))
    )
    (net (code "137") (name "Net-(B26-Pad+)") (class "Default")
      (node (ref "B26") (pin "+") (pinfunction "+_+") (pintype "passive"))
      (node (ref "B26") (pin "-") (pinfunction "-_-") (pintype "passive"))
    )
    (net (code "138") (name "Net-(B26-PadAC1)") (class "Default")
      (node (ref "B26") (pin "AC1") (pinfunction "AC1_AC1") (pintype "passive"))
      (node (ref "R34") (pin "2") (pinfunction "2_2") (pintype "passive"))
      (node (ref "X4") (pin "3") (pinfunction "3_3") (pintype "passive"))
    )
    (net (code "139") (name "Net-(B27-Pad+)") (class "Default")
      (node (ref "B27") (pin "+") (pinfunction "+_+") (pintype "passive"))
      (node (ref "B27") (pin "-") (pinfunction "-_-") (pintype "passive"))
    )
    (net (code "140") (name "Net-(B27-PadAC1)") (class "Default")
      (node (ref "B27") (pin "AC1") (pinfunction "AC1_AC1") (pintype "passive"))
      (node (ref "R35") (pin "2") (pinfunction "2_2") (pintype "passive"))
      (node (ref "X4") (pin "4") (pinfunction "4_4") (pintype "passive"))
    )
    (net (code "141") (name "Net-(B28-Pad+)") (class "Default")
      (node (ref "B28") (pin "+") (pinfunction "+_+") (pintype "passive"))
      (node (ref "B28") (pin "-") (pinfunction "-_-") (pintype "passive"))
    )
    (net (code "142") (name "Net-(B28-PadAC1)") (class "Default")
      (node (ref "B28") (pin "AC1") (pinfunction "AC1_AC1") (pintype "passive"))
      (node (ref "R36") (pin "2") (pinfunction "2_2") (pintype "passive"))
      (node (ref "X4") (pin "5") (pinfunction "5_5") (pintype "passive"))
    )
    (net (code "143") (name "Net-(B29-Pad+)") (class "Default")
      (node (ref "B29") (pin "+") (pinfunction "+_+") (pintype "passive"))
      (node (ref "B29") (pin "-") (pinfunction "-_-") (pintype "passive"))
    )
    (net (code "144") (name "Net-(B29-PadAC1)") (class "Default")
      (node (ref "B29") (pin "AC1") (pinfunction "AC1_AC1") (pintype "passive"))
      (node (ref "R37") (pin "2") (pinfunction "2_2") (pintype "passive"))
      (node (ref "X4") (pin "6") (pinfunction "6_6") (pintype "passive"))
    )
    (net (code "145") (name "Net-(B30-Pad+)") (class "Default")
      (node (ref "B30") (pin "+") (pinfunction "+_+") (pintype "passive"))
      (node (ref "B30") (pin "-") (pinfunction "-_-") (pintype "passive"))
    )
    (net (code "146") (name "Net-(B30-PadAC1)") (class "Default")
      (node (ref "B30") (pin "AC1") (pinfunction "AC1_AC1") (pintype "passive"))
      (node (ref "R38") (pin "2") (pinfunction "2_2") (pintype "passive"))
      (node (ref "X4") (pin "7") (pinfunction "7_7") (pintype "passive"))
    )
    (net (code "147") (name "Net-(B31-Pad+)") (class "Default")
      (node (ref "B31") (pin "+") (pinfunction "+_+") (pintype "passive"))
      (node (ref "B31") (pin "-") (pinfunction "-_-") (pintype "passive"))
    )
    (net (code "148") (name "Net-(B31-PadAC1)") (class "Default")
      (node (ref "B31") (pin "AC1") (pinfunction "AC1_AC1") (pintype "passive"))
      (node (ref "R39") (pin "2") (pinfunction "2_2") (pintype "passive"))
      (node (ref "X4") (pin "8") (pinfunction "8_8") (pintype "passive"))
    )
    (net (code "149") (name "Net-(B32-Pad+)") (class "Default")
      (node (ref "B32") (pin "+") (pinfunction "+_+") (pintype "passive"))
      (node (ref "B32") (pin "-") (pinfunction "-_-") (pintype "passive"))
    )
    (net (code "150") (name "Net-(B32-PadAC1)") (class "Default")
      (node (ref "B32") (pin "AC1") (pinfunction "AC1_AC1") (pintype "passive"))
      (node (ref "R40") (pin "2") (pinfunction "2_2") (pintype "passive"))
      (node (ref "X4") (pin "9") (pinfunction "9_9") (pintype "passive"))
    )
    (net (code "151") (name "Net-(IC1-(ICP1)_PD4)") (class "Default")
      (node (ref "IC1") (pin "47") (pinfunction "(ICP1)_PD4_47") (pintype "bidirectional"))
      (node (ref "S1") (pin "8") (pinfunction "8_8") (pintype "passive"))
    )
    (net (code "152") (name "Net-(IC1-(T0)_PD7)") (class "Default")
      (node (ref "IC1") (pin "50") (pinfunction "(T0)_PD7_50") (pintype "bidirectional"))
      (node (ref "S1") (pin "5") (pinfunction "5_5") (pintype "passive"))
    )
    (net (code "153") (name "Net-(IC1-(T1)_PD6)") (class "Default")
      (node (ref "IC1") (pin "49") (pinfunction "(T1)_PD6_49") (pintype "bidirectional"))
      (node (ref "S1") (pin "6") (pinfunction "6_6") (pintype "passive"))
    )
    (net (code "154") (name "Net-(IC1-(XCK1)_PD5)") (class "Default")
      (node (ref "IC1") (pin "48") (pinfunction "(XCK1)_PD5_48") (pintype "bidirectional"))
      (node (ref "S1") (pin "7") (pinfunction "7_7") (pintype "passive"))
    )
    (net (code "155") (name "Net-(IC4-PC0)") (class "Default")
      (node (ref "C44") (pin "1") (pinfunction "1_1") (pintype "passive"))
      (node (ref "IC4") (pin "2") (pinfunction "PC0_2") (pintype "bidirectional"))
      (node (ref "Q3") (pin "3") (pinfunction "2_3") (pintype "passive"))
      (node (ref "R41") (pin "2") (pinfunction "2_2") (pintype "passive"))
    )
    (net (code "156") (name "Net-(IC4-UCAP)") (class "Default")
      (node (ref "C45") (pin "1") (pinfunction "1_1") (pintype "passive"))
      (node (ref "IC4") (pin "27") (pinfunction "UCAP_27") (pintype "output"))
    )
    (net (code "157") (name "Net-(IC4-XTAL1)") (class "Default")
      (node (ref "C43") (pin "1") (pinfunction "1_1") (pintype "passive"))
      (node (ref "IC4") (pin "1") (pinfunction "XTAL1_1") (pintype "input"))
      (node (ref "Q3") (pin "1") (pinfunction "1_1") (pintype "passive"))
      (node (ref "R41") (pin "1") (pinfunction "1_1") (pintype "passive"))
    )
    (net (code "158") (name "Net-(J1-Pad1)") (class "Default")
      (node (ref "J1") (pin "1") (pinfunction "1_1") (pintype "passive"))
      (node (ref "J2") (pin "1") (pinfunction "1_1") (pintype "passive"))
    )
    (net (code "159") (name "Net-(J1-Pad2)") (class "Default")
      (node (ref "J1") (pin "2") (pinfunction "2_2") (pintype "passive"))
      (node (ref "J2") (pin "2") (pinfunction "2_2") (pintype "passive"))
    )
    (net (code "160") (name "Net-(OK1A-A)") (class "Default")
      (node (ref "C14") (pin "1") (pinfunction "1_1") (pintype "passive"))
      (node (ref "OK1") (pin "1") (pinfunction "A_1") (pintype "passive"))
      (node (ref "R12") (pin "1") (pinfunction "1_1") (pintype "passive"))
    )
    (net (code "161") (name "Net-(OK1B-A)") (class "Default")
      (node (ref "C13") (pin "1") (pinfunction "1_1") (pintype "passive"))
      (node (ref "OK1") (pin "3") (pinfunction "A_3") (pintype "passive"))
      (node (ref "R11") (pin "1") (pinfunction "1_1") (pintype "passive"))
    )
    (net (code "162") (name "Net-(OK1C-A)") (class "Default")
      (node (ref "C12") (pin "1") (pinfunction "1_1") (pintype "passive"))
      (node (ref "OK1") (pin "5") (pinfunction "A_5") (pintype "passive"))
      (node (ref "R10") (pin "1") (pinfunction "1_1") (pintype "passive"))
    )
    (net (code "163") (name "Net-(OK1D-A)") (class "Default")
      (node (ref "C11") (pin "1") (pinfunction "1_1") (pintype "passive"))
      (node (ref "OK1") (pin "7") (pinfunction "A_7") (pintype "passive"))
      (node (ref "R9") (pin "1") (pinfunction "1_1") (pintype "passive"))
    )
    (net (code "164") (name "Net-(OK2A-A)") (class "Default")
      (node (ref "C18") (pin "1") (pinfunction "1_1") (pintype "passive"))
      (node (ref "OK2") (pin "1") (pinfunction "A_1") (pintype "passive"))
      (node (ref "R16") (pin "1") (pinfunction "1_1") (pintype "passive"))
    )
    (net (code "165") (name "Net-(OK2B-A)") (class "Default")
      (node (ref "C17") (pin "1") (pinfunction "1_1") (pintype "passive"))
      (node (ref "OK2") (pin "3") (pinfunction "A_3") (pintype "passive"))
      (node (ref "R15") (pin "1") (pinfunction "1_1") (pintype "passive"))
    )
    (net (code "166") (name "Net-(OK2C-A)") (class "Default")
      (node (ref "C16") (pin "1") (pinfunction "1_1") (pintype "passive"))
      (node (ref "OK2") (pin "5") (pinfunction "A_5") (pintype "passive"))
      (node (ref "R14") (pin "1") (pinfunction "1_1") (pintype "passive"))
    )
    (net (code "167") (name "Net-(OK2D-A)") (class "Default")
      (node (ref "C15") (pin "1") (pinfunction "1_1") (pintype "passive"))
      (node (ref "OK2") (pin "7") (pinfunction "A_7") (pintype "passive"))
      (node (ref "R13") (pin "1") (pinfunction "1_1") (pintype "passive"))
    )
    (net (code "168") (name "Net-(OK3A-A)") (class "Default")
      (node (ref "C22") (pin "1") (pinfunction "1_1") (pintype "passive"))
      (node (ref "OK3") (pin "1") (pinfunction "A_1") (pintype "passive"))
      (node (ref "R20") (pin "1") (pinfunction "1_1") (pintype "passive"))
    )
    (net (code "169") (name "Net-(OK3B-A)") (class "Default")
      (node (ref "C21") (pin "1") (pinfunction "1_1") (pintype "passive"))
      (node (ref "OK3") (pin "3") (pinfunction "A_3") (pintype "passive"))
      (node (ref "R19") (pin "1") (pinfunction "1_1") (pintype "passive"))
    )
    (net (code "170") (name "Net-(OK3C-A)") (class "Default")
      (node (ref "C20") (pin "1") (pinfunction "1_1") (pintype "passive"))
      (node (ref "OK3") (pin "5") (pinfunction "A_5") (pintype "passive"))
      (node (ref "R18") (pin "1") (pinfunction "1_1") (pintype "passive"))
    )
    (net (code "171") (name "Net-(OK3D-A)") (class "Default")
      (node (ref "C19") (pin "1") (pinfunction "1_1") (pintype "passive"))
      (node (ref "OK3") (pin "7") (pinfunction "A_7") (pintype "passive"))
      (node (ref "R17") (pin "1") (pinfunction "1_1") (pintype "passive"))
    )
    (net (code "172") (name "Net-(OK4A-A)") (class "Default")
      (node (ref "C26") (pin "1") (pinfunction "1_1") (pintype "passive"))
      (node (ref "OK4") (pin "1") (pinfunction "A_1") (pintype "passive"))
      (node (ref "R24") (pin "1") (pinfunction "1_1") (pintype "passive"))
    )
    (net (code "173") (name "Net-(OK4B-A)") (class "Default")
      (node (ref "C25") (pin "1") (pinfunction "1_1") (pintype "passive"))
      (node (ref "OK4") (pin "3") (pinfunction "A_3") (pintype "passive"))
      (node (ref "R23") (pin "1") (pinfunction "1_1") (pintype "passive"))
    )
    (net (code "174") (name "Net-(OK4C-A)") (class "Default")
      (node (ref "C24") (pin "1") (pinfunction "1_1") (pintype "passive"))
      (node (ref "OK4") (pin "5") (pinfunction "A_5") (pintype "passive"))
      (node (ref "R22") (pin "1") (pinfunction "1_1") (pintype "passive"))
    )
    (net (code "175") (name "Net-(OK4D-A)") (class "Default")
      (node (ref "C23") (pin "1") (pinfunction "1_1") (pintype "passive"))
      (node (ref "OK4") (pin "7") (pinfunction "A_7") (pintype "passive"))
      (node (ref "R21") (pin "1") (pinfunction "1_1") (pintype "passive"))
    )
    (net (code "176") (name "Net-(OK5A-A)") (class "Default")
      (node (ref "C30") (pin "1") (pinfunction "1_1") (pintype "passive"))
      (node (ref "OK5") (pin "1") (pinfunction "A_1") (pintype "passive"))
      (node (ref "R28") (pin "1") (pinfunction "1_1") (pintype "passive"))
    )
    (net (code "177") (name "Net-(OK5B-A)") (class "Default")
      (node (ref "C29") (pin "1") (pinfunction "1_1") (pintype "passive"))
      (node (ref "OK5") (pin "3") (pinfunction "A_3") (pintype "passive"))
      (node (ref "R27") (pin "1") (pinfunction "1_1") (pintype "passive"))
    )
    (net (code "178") (name "Net-(OK5C-A)") (class "Default")
      (node (ref "C28") (pin "1") (pinfunction "1_1") (pintype "passive"))
      (node (ref "OK5") (pin "5") (pinfunction "A_5") (pintype "passive"))
      (node (ref "R26") (pin "1") (pinfunction "1_1") (pintype "passive"))
    )
    (net (code "179") (name "Net-(OK5D-A)") (class "Default")
      (node (ref "C27") (pin "1") (pinfunction "1_1") (pintype "passive"))
      (node (ref "OK5") (pin "7") (pinfunction "A_7") (pintype "passive"))
      (node (ref "R25") (pin "1") (pinfunction "1_1") (pintype "passive"))
    )
    (net (code "180") (name "Net-(OK6A-A)") (class "Default")
      (node (ref "C34") (pin "1") (pinfunction "1_1") (pintype "passive"))
      (node (ref "OK6") (pin "1") (pinfunction "A_1") (pintype "passive"))
      (node (ref "R32") (pin "1") (pinfunction "1_1") (pintype "passive"))
    )
    (net (code "181") (name "Net-(OK6B-A)") (class "Default")
      (node (ref "C33") (pin "1") (pinfunction "1_1") (pintype "passive"))
      (node (ref "OK6") (pin "3") (pinfunction "A_3") (pintype "passive"))
      (node (ref "R31") (pin "1") (pinfunction "1_1") (pintype "passive"))
    )
    (net (code "182") (name "Net-(OK6C-A)") (class "Default")
      (node (ref "C32") (pin "1") (pinfunction "1_1") (pintype "passive"))
      (node (ref "OK6") (pin "5") (pinfunction "A_5") (pintype "passive"))
      (node (ref "R30") (pin "1") (pinfunction "1_1") (pintype "passive"))
    )
    (net (code "183") (name "Net-(OK6D-A)") (class "Default")
      (node (ref "C31") (pin "1") (pinfunction "1_1") (pintype "passive"))
      (node (ref "OK6") (pin "7") (pinfunction "A_7") (pintype "passive"))
      (node (ref "R29") (pin "1") (pinfunction "1_1") (pintype "passive"))
    )
    (net (code "184") (name "Net-(OK7A-A)") (class "Default")
      (node (ref "C38") (pin "1") (pinfunction "1_1") (pintype "passive"))
      (node (ref "OK7") (pin "1") (pinfunction "A_1") (pintype "passive"))
      (node (ref "R36") (pin "1") (pinfunction "1_1") (pintype "passive"))
    )
    (net (code "185") (name "Net-(OK7B-A)") (class "Default")
      (node (ref "C37") (pin "1") (pinfunction "1_1") (pintype "passive"))
      (node (ref "OK7") (pin "3") (pinfunction "A_3") (pintype "passive"))
      (node (ref "R35") (pin "1") (pinfunction "1_1") (pintype "passive"))
    )
    (net (code "186") (name "Net-(OK7C-A)") (class "Default")
      (node (ref "C36") (pin "1") (pinfunction "1_1") (pintype "passive"))
      (node (ref "OK7") (pin "5") (pinfunction "A_5") (pintype "passive"))
      (node (ref "R34") (pin "1") (pinfunction "1_1") (pintype "passive"))
    )
    (net (code "187") (name "Net-(OK7D-A)") (class "Default")
      (node (ref "C35") (pin "1") (pinfunction "1_1") (pintype "passive"))
      (node (ref "OK7") (pin "7") (pinfunction "A_7") (pintype "passive"))
      (node (ref "R33") (pin "1") (pinfunction "1_1") (pintype "passive"))
    )
    (net (code "188") (name "Net-(OK8A-A)") (class "Default")
      (node (ref "C42") (pin "1") (pinfunction "1_1") (pintype "passive"))
      (node (ref "OK8") (pin "1") (pinfunction "A_1") (pintype "passive"))
      (node (ref "R40") (pin "1") (pinfunction "1_1") (pintype "passive"))
    )
    (net (code "189") (name "Net-(OK8B-A)") (class "Default")
      (node (ref "C41") (pin "1") (pinfunction "1_1") (pintype "passive"))
      (node (ref "OK8") (pin "3") (pinfunction "A_3") (pintype "passive"))
      (node (ref "R39") (pin "1") (pinfunction "1_1") (pintype "passive"))
    )
    (net (code "190") (name "Net-(OK8C-A)") (class "Default")
      (node (ref "C40") (pin "1") (pinfunction "1_1") (pintype "passive"))
      (node (ref "OK8") (pin "5") (pinfunction "A_5") (pintype "passive"))
      (node (ref "R38") (pin "1") (pinfunction "1_1") (pintype "passive"))
    )
    (net (code "191") (name "Net-(OK8D-A)") (class "Default")
      (node (ref "C39") (pin "1") (pinfunction "1_1") (pintype "passive"))
      (node (ref "OK8") (pin "7") (pinfunction "A_7") (pintype "passive"))
      (node (ref "R37") (pin "1") (pinfunction "1_1") (pintype "passive"))
    )
    (net (code "192") (name "Net-(OK9-C)") (class "Default")
      (node (ref "OK9") (pin "2") (pinfunction "C_2") (pintype "passive"))
      (node (ref "R46") (pin "1") (pinfunction "1_1") (pintype "passive"))
    )
    (net (code "193") (name "Net-(OK9-COL)") (class "Default")
      (node (ref "C46") (pin "1") (pinfunction "1_1") (pintype "passive"))
      (node (ref "OK9") (pin "4") (pinfunction "COL_4") (pintype "passive"))
      (node (ref "R45") (pin "1") (pinfunction "1_1") (pintype "passive"))
    )
    (net (code "194") (name "Net-(POWER-PadC)") (class "Default")
      (node (ref "POWER") (pin "C") (pinfunction "C_C") (pintype "passive"))
      (node (ref "R4") (pin "1") (pinfunction "1_1") (pintype "passive"))
    )
    (net (code "195") (name "Net-(R3-Pad2)") (class "Default")
      (node (ref "R3") (pin "2") (pinfunction "2_2") (pintype "passive"))
      (node (ref "TERM") (pin "1") (pinfunction "1_1") (pintype "passive"))
    )
    (net (code "196") (name "Net-(R5-Pad1)") (class "Default")
      (node (ref "R5") (pin "1") (pinfunction "1_1") (pintype "passive"))
      (node (ref "STATUS") (pin "C") (pinfunction "C_C") (pintype "passive"))
    )
    (net (code "197") (name "Net-(R42-Pad2)") (class "Default")
      (node (ref "R42") (pin "2") (pinfunction "2_2") (pintype "passive"))
      (node (ref "X6") (pin "2") (pinfunction "2_2") (pintype "passive"))
    )
    (net (code "198") (name "Net-(R43-Pad2)") (class "Default")
      (node (ref "R43") (pin "2") (pinfunction "2_2") (pintype "passive"))
      (node (ref "X6") (pin "3") (pinfunction "3_3") (pintype "passive"))
    )
    (net (code "199") (name "Net-(R47-Pad1)") (class "Default")
      (node (ref "R47") (pin "1") (pinfunction "1_1") (pintype "passive"))
      (node (ref "USBRX") (pin "C") (pinfunction "C_C") (pintype "passive"))
    )
    (net (code "200") (name "Net-(R48-Pad1)") (class "Default")
      (node (ref "R48") (pin "1") (pinfunction "1_1") (pintype "passive"))
      (node (ref "USBTX") (pin "C") (pinfunction "C_C") (pintype "passive"))
    )
    (net (code "201") (name "Net-(RN1-Pad1)") (class "Default")
      (node (ref "RN1") (pin "1") (pinfunction "1_1") (pintype "passive"))
      (node (ref "T1") (pin "A") (pinfunction "A_A") (pintype "passive"))
    )
    (net (code "202") (name "Net-(RN1B-1)") (class "Default")
      (node (ref "RN1") (pin "2") (pinfunction "1_2") (pintype "passive"))
      (node (ref "T2") (pin "A") (pinfunction "A_A") (pintype "passive"))
    )
    (net (code "203") (name "Net-(RN1C-1)") (class "Default")
      (node (ref "RN1") (pin "3") (pinfunction "1_3") (pintype "passive"))
      (node (ref "T3") (pin "A") (pinfunction "A_A") (pintype "passive"))
    )
    (net (code "204") (name "Net-(RN1D-1)") (class "Default")
      (node (ref "RN1") (pin "4") (pinfunction "1_4") (pintype "passive"))
      (node (ref "T4") (pin "A") (pinfunction "A_A") (pintype "passive"))
    )
    (net (code "205") (name "Net-(RN2-Pad1)") (class "Default")
      (node (ref "RN2") (pin "1") (pinfunction "1_1") (pintype "passive"))
      (node (ref "T5") (pin "A") (pinfunction "A_A") (pintype "passive"))
    )
    (net (code "206") (name "Net-(RN2B-1)") (class "Default")
      (node (ref "RN2") (pin "2") (pinfunction "1_2") (pintype "passive"))
      (node (ref "T6") (pin "A") (pinfunction "A_A") (pintype "passive"))
    )
    (net (code "207") (name "Net-(RN2C-1)") (class "Default")
      (node (ref "RN2") (pin "3") (pinfunction "1_3") (pintype "passive"))
      (node (ref "T7") (pin "A") (pinfunction "A_A") (pintype "passive"))
    )
    (net (code "208") (name "Net-(RN2D-1)") (class "Default")
      (node (ref "RN2") (pin "4") (pinfunction "1_4") (pintype "passive"))
      (node (ref "T8") (pin "A") (pinfunction "A_A") (pintype "passive"))
    )
    (net (code "209") (name "Net-(RN3-Pad1)") (class "Default")
      (node (ref "RN3") (pin "1") (pinfunction "1_1") (pintype "passive"))
      (node (ref "T9") (pin "A") (pinfunction "A_A") (pintype "passive"))
    )
    (net (code "210") (name "Net-(RN3B-1)") (class "Default")
      (node (ref "RN3") (pin "2") (pinfunction "1_2") (pintype "passive"))
      (node (ref "T10") (pin "A") (pinfunction "A_A") (pintype "passive"))
    )
    (net (code "211") (name "Net-(RN3C-1)") (class "Default")
      (node (ref "RN3") (pin "3") (pinfunction "1_3") (pintype "passive"))
      (node (ref "T11") (pin "A") (pinfunction "A_A") (pintype "passive"))
    )
    (net (code "212") (name "Net-(RN3D-1)") (class "Default")
      (node (ref "RN3") (pin "4") (pinfunction "1_4") (pintype "passive"))
      (node (ref "T12") (pin "A") (pinfunction "A_A") (pintype "passive"))
    )
    (net (code "213") (name "Net-(RN4-Pad1)") (class "Default")
      (node (ref "RN4") (pin "1") (pinfunction "1_1") (pintype "passive"))
      (node (ref "T13") (pin "A") (pinfunction "A_A") (pintype "passive"))
    )
    (net (code "214") (name "Net-(RN4B-1)") (class "Default")
      (node (ref "RN4") (pin "2") (pinfunction "1_2") (pintype "passive"))
      (node (ref "T14") (pin "A") (pinfunction "A_A") (pintype "passive"))
    )
    (net (code "215") (name "Net-(RN4C-1)") (class "Default")
      (node (ref "RN4") (pin "3") (pinfunction "1_3") (pintype "passive"))
      (node (ref "T15") (pin "A") (pinfunction "A_A") (pintype "passive"))
    )
    (net (code "216") (name "Net-(RN4D-1)") (class "Default")
      (node (ref "RN4") (pin "4") (pinfunction "1_4") (pintype "passive"))
      (node (ref "T16") (pin "A") (pinfunction "A_A") (pintype "passive"))
    )
    (net (code "217") (name "Net-(RN5-Pad1)") (class "Default")
      (node (ref "RN5") (pin "1") (pinfunction "1_1") (pintype "passive"))
      (node (ref "T17") (pin "A") (pinfunction "A_A") (pintype "passive"))
    )
    (net (code "218") (name "Net-(RN5B-1)") (class "Default")
      (node (ref "RN5") (pin "2") (pinfunction "1_2") (pintype "passive"))
      (node (ref "T18") (pin "A") (pinfunction "A_A") (pintype "passive"))
    )
    (net (code "219") (name "Net-(RN5C-1)") (class "Default")
      (node (ref "RN5") (pin "3") (pinfunction "1_3") (pintype "passive"))
      (node (ref "T19") (pin "A") (pinfunction "A_A") (pintype "passive"))
    )
    (net (code "220") (name "Net-(RN5D-1)") (class "Default")
      (node (ref "RN5") (pin "4") (pinfunction "1_4") (pintype "passive"))
      (node (ref "T20") (pin "A") (pinfunction "A_A") (pintype "passive"))
    )
    (net (code "221") (name "Net-(RN6-Pad1)") (class "Default")
      (node (ref "RN6") (pin "1") (pinfunction "1_1") (pintype "passive"))
      (node (ref "T21") (pin "A") (pinfunction "A_A") (pintype "passive"))
    )
    (net (code "222") (name "Net-(RN6B-1)") (class "Default")
      (node (ref "RN6") (pin "2") (pinfunction "1_2") (pintype "passive"))
      (node (ref "T22") (pin "A") (pinfunction "A_A") (pintype "passive"))
    )
    (net (code "223") (name "Net-(RN6C-1)") (class "Default")
      (node (ref "RN6") (pin "3") (pinfunction "1_3") (pintype "passive"))
      (node (ref "T23") (pin "A") (pinfunction "A_A") (pintype "passive"))
    )
    (net (code "224") (name "Net-(RN6D-1)") (class "Default")
      (node (ref "RN6") (pin "4") (pinfunction "1_4") (pintype "passive"))
      (node (ref "T24") (pin "A") (pinfunction "A_A") (pintype "passive"))
    )
    (net (code "225") (name "Net-(RN7-Pad1)") (class "Default")
      (node (ref "RN7") (pin "1") (pinfunction "1_1") (pintype "passive"))
      (node (ref "T25") (pin "A") (pinfunction "A_A") (pintype "passive"))
    )
    (net (code "226") (name "Net-(RN7B-1)") (class "Default")
      (node (ref "RN7") (pin "2") (pinfunction "1_2") (pintype "passive"))
      (node (ref "T26") (pin "A") (pinfunction "A_A") (pintype "passive"))
    )
    (net (code "227") (name "Net-(RN7C-1)") (class "Default")
      (node (ref "RN7") (pin "3") (pinfunction "1_3") (pintype "passive"))
      (node (ref "T27") (pin "A") (pinfunction "A_A") (pintype "passive"))
    )
    (net (code "228") (name "Net-(RN7D-1)") (class "Default")
      (node (ref "RN7") (pin "4") (pinfunction "1_4") (pintype "passive"))
      (node (ref "T28") (pin "A") (pinfunction "A_A") (pintype "passive"))
    )
    (net (code "229") (name "Net-(RN8-Pad1)") (class "Default")
      (node (ref "RN8") (pin "1") (pinfunction "1_1") (pintype "passive"))
      (node (ref "T29") (pin "A") (pinfunction "A_A") (pintype "passive"))
    )
    (net (code "230") (name "Net-(RN8B-1)") (class "Default")
      (node (ref "RN8") (pin "2") (pinfunction "1_2") (pintype "passive"))
      (node (ref "T30") (pin "A") (pinfunction "A_A") (pintype "passive"))
    )
    (net (code "231") (name "Net-(RN8C-1)") (class "Default")
      (node (ref "RN8") (pin "3") (pinfunction "1_3") (pintype "passive"))
      (node (ref "T31") (pin "A") (pinfunction "A_A") (pintype "passive"))
    )
    (net (code "232") (name "Net-(RN8D-1)") (class "Default")
      (node (ref "RN8") (pin "4") (pinfunction "1_4") (pintype "passive"))
      (node (ref "T32") (pin "A") (pinfunction "A_A") (pintype "passive"))
    )
    (net (code "233") (name "OSC1") (class "Default")
      (node (ref "C7") (pin "1") (pinfunction "1_1") (pintype "passive"))
      (node (ref "IC3") (pin "8") (pinfunction "OSC1_8") (pintype "input"))
      (node (ref "Q2") (pin "1") (pinfunction "1_1") (pintype "passive"))
      (node (ref "R2") (pin "1") (pinfunction "1_1") (pintype "passive"))
    )
    (net (code "234") (name "OSC2") (class "Default")
      (node (ref "C8") (pin "1") (pinfunction "1_1") (pintype "passive"))
      (node (ref "IC3") (pin "7") (pinfunction "OSC2_7") (pintype "output"))
      (node (ref "Q2") (pin "3") (pinfunction "2_3") (pintype "passive"))
      (node (ref "R2") (pin "2") (pinfunction "2_2") (pintype "passive"))
    )
    (net (code "235") (name "RESET") (class "Default")
      (node (ref "C46") (pin "2") (pinfunction "2_2") (pintype "passive"))
      (node (ref "IC1") (pin "30") (pinfunction "~{RESET}_30") (pintype "input"))
      (node (ref "IC3") (pin "17") (pinfunction "~{RESET}_17") (pintype "input"))
      (node (ref "ISP") (pin "5") (pinfunction "S_5") (pintype "passive"))
      (node (ref "R8") (pin "1") (pinfunction "1_1") (pintype "passive"))
      (node (ref "U$15") (pin "P$3") (pinfunction "P$3_P$3") (pintype "bidirectional"))
      (node (ref "U$15") (pin "P$4") (pinfunction "P$4_P$4") (pintype "bidirectional"))
    )
    (net (code "236") (name "RESET2") (class "Default")
      (node (ref "IC4") (pin "24") (pinfunction "PC1//~{RESET}_24") (pintype "bidirectional"))
      (node (ref "R44") (pin "2") (pinfunction "2_2") (pintype "passive"))
      (node (ref "RS") (pin "TP") (pinfunction "TP_TP") (pintype "input"))
    )
    (net (code "237") (name "RXCAN") (class "Default")
      (node (ref "IC2") (pin "4") (pinfunction "RXD_4") (pintype "output"))
      (node (ref "IC3") (pin "2") (pinfunction "RXCAN_2") (pintype "input"))
    )
    (net (code "238") (name "RXD") (class "Default")
      (node (ref "IC1") (pin "2") (pinfunction "(RXD0/PCINT8)_PE0_2") (pintype "bidirectional"))
      (node (ref "IC5") (pin "2") (pinfunction "VOA_2") (pintype "output"))
    )
    (net (code "239") (name "RXDUSB") (class "Default")
      (node (ref "IC4") (pin "8") (pinfunction "PD2_8") (pintype "bidirectional"))
      (node (ref "IC5") (pin "6") (pinfunction "VOB_6") (pintype "output"))
    )
    (net (code "240") (name "RXLED") (class "Default")
      (node (ref "IC4") (pin "10") (pinfunction "PD4_10") (pintype "bidirectional"))
      (node (ref "R47") (pin "2") (pinfunction "2_2") (pintype "passive"))
    )
    (net (code "241") (name "SCK") (class "Default")
      (node (ref "IC1") (pin "20") (pinfunction "(SCK/PCINT1)_PB1_20") (pintype "bidirectional"))
      (node (ref "IC3") (pin "13") (pinfunction "SCK_13") (pintype "input"))
      (node (ref "ISP") (pin "3") (pinfunction "S_3") (pintype "passive"))
    )
    (net (code "242") (name "SCK2") (class "Default")
      (node (ref "IC4") (pin "15") (pinfunction "PB1_15") (pintype "bidirectional"))
      (node (ref "SCK") (pin "TP") (pinfunction "TP_TP") (pintype "input"))
    )
    (net (code "243") (name "SCL") (class "Default")
      (node (ref "IC1") (pin "43") (pinfunction "(SCL/INT0)_PD0_43") (pintype "bidirectional"))
      (node (ref "I²C") (pin "2") (pinfunction "S_2") (pintype "passive"))
      (node (ref "R6") (pin "1") (pinfunction "1_1") (pintype "passive"))
    )
    (net (code "244") (name "SDA") (class "Default")
      (node (ref "IC1") (pin "44") (pinfunction "(SDA/INT1)_PD1_44") (pintype "bidirectional"))
      (node (ref "I²C") (pin "1") (pinfunction "S_1") (pintype "passive"))
      (node (ref "R7") (pin "1") (pinfunction "1_1") (pintype "passive"))
    )
    (net (code "245") (name "STATUS") (class "Default")
      (node (ref "IC1") (pin "46") (pinfunction "(TXD1/INT3)_PD3_46") (pintype "bidirectional"))
      (node (ref "STATUS") (pin "A") (pinfunction "A_A") (pintype "passive"))
    )
    (net (code "246") (name "TXCAN") (class "Default")
      (node (ref "IC2") (pin "1") (pinfunction "TXD_1") (pintype "input"))
      (node (ref "IC3") (pin "1") (pinfunction "TXCAN_1") (pintype "output"))
    )
    (net (code "247") (name "TXD") (class "Default")
      (node (ref "IC1") (pin "3") (pinfunction "(TXD0)_PE1_3") (pintype "bidirectional"))
      (node (ref "IC5") (pin "3") (pinfunction "VIB_3") (pintype "input"))
    )
    (net (code "248") (name "TXDUSB") (class "Default")
      (node (ref "IC4") (pin "9") (pinfunction "PD3_9") (pintype "bidirectional"))
      (node (ref "IC5") (pin "7") (pinfunction "VIA_7") (pintype "input"))
    )
    (net (code "249") (name "TXLED") (class "Default")
      (node (ref "IC4") (pin "11") (pinfunction "PD5_11") (pintype "bidirectional"))
      (node (ref "R48") (pin "2") (pinfunction "2_2") (pintype "passive"))
    )
    (net (code "250") (name "VCC") (class "Default")
      (node (ref "C1") (pin "1") (pinfunction "1_1") (pintype "passive"))
      (node (ref "C10") (pin "1") (pinfunction "1_1") (pintype "passive"))
      (node (ref "C2") (pin "1") (pinfunction "1_1") (pintype "passive"))
      (node (ref "C3") (pin "1") (pinfunction "1_1") (pintype "passive"))
      (node (ref "C6") (pin "1") (pinfunction "1_1") (pintype "passive"))
      (node (ref "IC1") (pin "10") (pinfunction "VCC_3_10") (pintype "power_in"))
      (node (ref "IC1") (pin "100") (pinfunction "AVCC_100") (pintype "power_in"))
      (node (ref "IC1") (pin "31") (pinfunction "VCC_2_31") (pintype "power_in"))
      (node (ref "IC1") (pin "61") (pinfunction "VCC_4_61") (pintype "power_in"))
      (node (ref "IC1") (pin "80") (pinfunction "VCC_80") (pintype "power_in"))
      (node (ref "IC2") (pin "3") (pinfunction "VDD_3") (pintype "power_in"))
      (node (ref "IC2") (pin "5") (pinfunction "VREF_5") (pintype "output"))
      (node (ref "IC3") (pin "18") (pinfunction "VDD_18") (pintype "power_in"))
      (node (ref "IC5") (pin "1") (pinfunction "VDD1_1") (pintype "power_in"))
      (node (ref "IC8") (pin "2") (pinfunction "VO_2") (pintype "passive"))
      (node (ref "ISP") (pin "2") (pinfunction "S_2") (pintype "passive"))
      (node (ref "POWER") (pin "A") (pinfunction "A_A") (pintype "passive"))
      (node (ref "R45") (pin "2") (pinfunction "2_2") (pintype "passive"))
      (node (ref "R6") (pin "2") (pinfunction "2_2") (pintype "passive"))
      (node (ref "R7") (pin "2") (pinfunction "2_2") (pintype "passive"))
      (node (ref "R8") (pin "2") (pinfunction "2_2") (pintype "passive"))
      (node (ref "RN1") (pin "5") (pinfunction "2_5") (pintype "passive"))
      (node (ref "RN1") (pin "6") (pinfunction "2_6") (pintype "passive"))
      (node (ref "RN1") (pin "7") (pinfunction "2_7") (pintype "passive"))
      (node (ref "RN1") (pin "8") (pinfunction "2_8") (pintype "passive"))
      (node (ref "RN2") (pin "5") (pinfunction "2_5") (pintype "passive"))
      (node (ref "RN2") (pin "6") (pinfunction "2_6") (pintype "passive"))
      (node (ref "RN2") (pin "7") (pinfunction "2_7") (pintype "passive"))
      (node (ref "RN2") (pin "8") (pinfunction "2_8") (pintype "passive"))
      (node (ref "RN3") (pin "5") (pinfunction "2_5") (pintype "passive"))
      (node (ref "RN3") (pin "6") (pinfunction "2_6") (pintype "passive"))
      (node (ref "RN3") (pin "7") (pinfunction "2_7") (pintype "passive"))
      (node (ref "RN3") (pin "8") (pinfunction "2_8") (pintype "passive"))
      (node (ref "RN4") (pin "5") (pinfunction "2_5") (pintype "passive"))
      (node (ref "RN4") (pin "6") (pinfunction "2_6") (pintype "passive"))
      (node (ref "RN4") (pin "7") (pinfunction "2_7") (pintype "passive"))
      (node (ref "RN4") (pin "8") (pinfunction "2_8") (pintype "passive"))
      (node (ref "RN5") (pin "5") (pinfunction "2_5") (pintype "passive"))
      (node (ref "RN5") (pin "6") (pinfunction "2_6") (pintype "passive"))
      (node (ref "RN5") (pin "7") (pinfunction "2_7") (pintype "passive"))
      (node (ref "RN5") (pin "8") (pinfunction "2_8") (pintype "passive"))
      (node (ref "RN6") (pin "5") (pinfunction "2_5") (pintype "passive"))
      (node (ref "RN6") (pin "6") (pinfunction "2_6") (pintype "passive"))
      (node (ref "RN6") (pin "7") (pinfunction "2_7") (pintype "passive"))
      (node (ref "RN6") (pin "8") (pinfunction "2_8") (pintype "passive"))
      (node (ref "RN7") (pin "5") (pinfunction "2_5") (pintype "passive"))
      (node (ref "RN7") (pin "6") (pinfunction "2_6") (pintype "passive"))
      (node (ref "RN7") (pin "7") (pinfunction "2_7") (pintype "passive"))
      (node (ref "RN7") (pin "8") (pinfunction "2_8") (pintype "passive"))
      (node (ref "RN8") (pin "5") (pinfunction "2_5") (pintype "passive"))
      (node (ref "RN8") (pin "6") (pinfunction "2_6") (pintype "passive"))
      (node (ref "RN8") (pin "7") (pinfunction "2_7") (pintype "passive"))
      (node (ref "RN8") (pin "8") (pinfunction "2_8") (pintype "passive"))
    )
    (net (code "251") (name "VCC2") (class "Default")
      (node (ref "C47") (pin "1") (pinfunction "1_1") (pintype "passive"))
      (node (ref "IC4") (pin "31") (pinfunction "UVCC_31") (pintype "power_in"))
      (node (ref "IC4") (pin "32") (pinfunction "AVCC_32") (pintype "power_in"))
      (node (ref "IC4") (pin "4") (pinfunction "VCC_4") (pintype "power_in"))
      (node (ref "IC5") (pin "8") (pinfunction "VDD2_8") (pintype "power_in"))
      (node (ref "OK9") (pin "1") (pinfunction "A_1") (pintype "passive"))
      (node (ref "R44") (pin "1") (pinfunction "1_1") (pintype "passive"))
      (node (ref "USBRX") (pin "A") (pinfunction "A_A") (pintype "passive"))
      (node (ref "USBTX") (pin "A") (pinfunction "A_A") (pintype "passive"))
      (node (ref "VCC") (pin "TP") (pinfunction "TP_TP") (pintype "input"))
      (node (ref "X6") (pin "1") (pinfunction "1_1") (pintype "passive"))
    )
    (net (code "252") (name "XTAL1") (class "Default")
      (node (ref "C4") (pin "1") (pinfunction "1_1") (pintype "passive"))
      (node (ref "IC1") (pin "34") (pinfunction "XTAL1_34") (pintype "input"))
      (node (ref "Q1") (pin "1") (pinfunction "1_1") (pintype "passive"))
      (node (ref "R1") (pin "1") (pinfunction "1_1") (pintype "passive"))
    )
    (net (code "253") (name "XTAL2") (class "Default")
      (node (ref "C5") (pin "1") (pinfunction "1_1") (pintype "passive"))
      (node (ref "IC1") (pin "33") (pinfunction "XTAL2_33") (pintype "output"))
      (node (ref "Q1") (pin "3") (pinfunction "2_3") (pintype "passive"))
      (node (ref "R1") (pin "2") (pinfunction "2_2") (pintype "passive"))
    )
    (net (code "254") (name "unconnected-(H1-MOUNT-PadB3,2)") (class "Default")
      (node (ref "H1") (pin "B3,2") (pinfunction "MOUNT_B3,2") (pintype "passive"))
    )
    (net (code "255") (name "unconnected-(H2-MOUNT-PadB3,2)") (class "Default")
      (node (ref "H2") (pin "B3,2") (pinfunction "MOUNT_B3,2") (pintype "passive"))
    )
    (net (code "256") (name "unconnected-(H3-MOUNT-PadB3,2)") (class "Default")
      (node (ref "H3") (pin "B3,2") (pinfunction "MOUNT_B3,2") (pintype "passive"))
    )
    (net (code "257") (name "unconnected-(H4-MOUNT-PadB3,2)") (class "Default")
      (node (ref "H4") (pin "B3,2") (pinfunction "MOUNT_B3,2") (pintype "passive"))
    )
    (net (code "258") (name "unconnected-(H5-MOUNT-PadB3,2)") (class "Default")
      (node (ref "H5") (pin "B3,2") (pinfunction "MOUNT_B3,2") (pintype "passive"))
    )
    (net (code "259") (name "unconnected-(H6-MOUNT-PadB3,2)") (class "Default")
      (node (ref "H6") (pin "B3,2") (pinfunction "MOUNT_B3,2") (pintype "passive"))
    )
    (net (code "260") (name "unconnected-(IC1-(OC0B)_PG5-Pad1)") (class "Default")
      (node (ref "IC1") (pin "1") (pinfunction "(OC0B)_PG5_1") (pintype "bidirectional"))
    )
    (net (code "261") (name "unconnected-(IC1-(OC1A{slash}PCINT5)_PB5-Pad24)") (class "Default")
      (node (ref "IC1") (pin "24") (pinfunction "(OC1A/PCINT5)_PB5_24") (pintype "bidirectional"))
    )
    (net (code "262") (name "unconnected-(IC1-(OC2A{slash}PCINT4)_PB4-Pad23)") (class "Default")
      (node (ref "IC1") (pin "23") (pinfunction "(OC2A/PCINT4)_PB4_23") (pintype "bidirectional"))
    )
    (net (code "263") (name "unconnected-(IC1-(TOSC1)_PG4-Pad29)") (class "Default")
      (node (ref "IC1") (pin "29") (pinfunction "(TOSC1)_PG4_29") (pintype "bidirectional"))
    )
    (net (code "264") (name "unconnected-(IC1-(TOSC2)_PG3-Pad28)") (class "Default")
      (node (ref "IC1") (pin "28") (pinfunction "(TOSC2)_PG3_28") (pintype "bidirectional"))
    )
    (net (code "265") (name "unconnected-(IC1-AREF-Pad98)") (class "Default")
      (node (ref "IC1") (pin "98") (pinfunction "AREF_98") (pintype "input"))
    )
    (net (code "266") (name "unconnected-(IC1-PG0_(~{WR})-Pad51)") (class "Default")
      (node (ref "IC1") (pin "51") (pinfunction "PG0_(~{WR})_51") (pintype "bidirectional"))
    )
    (net (code "267") (name "unconnected-(IC1-PG1_(~{RD})-Pad52)") (class "Default")
      (node (ref "IC1") (pin "52") (pinfunction "PG1_(~{RD})_52") (pintype "bidirectional"))
    )
    (net (code "268") (name "unconnected-(IC1-PG2_(ALE)-Pad70)") (class "Default")
      (node (ref "IC1") (pin "70") (pinfunction "PG2_(ALE)_70") (pintype "bidirectional"))
    )
    (net (code "269") (name "unconnected-(IC3-CLKOUT{slash}SOF-Pad3)") (class "Default")
      (node (ref "IC3") (pin "3") (pinfunction "CLKOUT/SOF_3") (pintype "output"))
    )
    (net (code "270") (name "unconnected-(IC3-~{RX0BF}-Pad11)") (class "Default")
      (node (ref "IC3") (pin "11") (pinfunction "~{RX0BF}_11") (pintype "output"))
    )
    (net (code "271") (name "unconnected-(IC3-~{RX1BF}-Pad10)") (class "Default")
      (node (ref "IC3") (pin "10") (pinfunction "~{RX1BF}_10") (pintype "output"))
    )
    (net (code "272") (name "unconnected-(IC3-~{TX0RTS}-Pad4)") (class "Default")
      (node (ref "IC3") (pin "4") (pinfunction "~{TX0RTS}_4") (pintype "input"))
    )
    (net (code "273") (name "unconnected-(IC3-~{TX1RTS}-Pad5)") (class "Default")
      (node (ref "IC3") (pin "5") (pinfunction "~{TX1RTS}_5") (pintype "input"))
    )
    (net (code "274") (name "unconnected-(IC3-~{TX2RTS}-Pad6)") (class "Default")
      (node (ref "IC3") (pin "6") (pinfunction "~{TX2RTS}_6") (pintype "input"))
    )
    (net (code "275") (name "unconnected-(IC4-PB0-Pad14)") (class "Default")
      (node (ref "IC4") (pin "14") (pinfunction "PB0_14") (pintype "bidirectional"))
    )
    (net (code "276") (name "unconnected-(IC4-PB4-Pad18)") (class "Default")
      (node (ref "IC4") (pin "18") (pinfunction "PB4_18") (pintype "bidirectional"))
    )
    (net (code "277") (name "unconnected-(IC4-PB5-Pad19)") (class "Default")
      (node (ref "IC4") (pin "19") (pinfunction "PB5_19") (pintype "bidirectional"))
    )
    (net (code "278") (name "unconnected-(IC4-PB6-Pad20)") (class "Default")
      (node (ref "IC4") (pin "20") (pinfunction "PB6_20") (pintype "bidirectional"))
    )
    (net (code "279") (name "unconnected-(IC4-PB7-Pad21)") (class "Default")
      (node (ref "IC4") (pin "21") (pinfunction "PB7_21") (pintype "bidirectional"))
    )
    (net (code "280") (name "unconnected-(IC4-PC2-Pad5)") (class "Default")
      (node (ref "IC4") (pin "5") (pinfunction "PC2_5") (pintype "bidirectional"))
    )
    (net (code "281") (name "unconnected-(IC4-PC4-Pad26)") (class "Default")
      (node (ref "IC4") (pin "26") (pinfunction "PC4_26") (pintype "bidirectional"))
    )
    (net (code "282") (name "unconnected-(IC4-PC5-Pad25)") (class "Default")
      (node (ref "IC4") (pin "25") (pinfunction "PC5_25") (pintype "bidirectional"))
    )
    (net (code "283") (name "unconnected-(IC4-PC6-Pad23)") (class "Default")
      (node (ref "IC4") (pin "23") (pinfunction "PC6_23") (pintype "bidirectional"))
    )
    (net (code "284") (name "unconnected-(IC4-PC7-Pad22)") (class "Default")
      (node (ref "IC4") (pin "22") (pinfunction "PC7_22") (pintype "bidirectional"))
    )
    (net (code "285") (name "unconnected-(IC4-PD0-Pad6)") (class "Default")
      (node (ref "IC4") (pin "6") (pinfunction "PD0_6") (pintype "bidirectional"))
    )
    (net (code "286") (name "unconnected-(IC4-PD1-Pad7)") (class "Default")
      (node (ref "IC4") (pin "7") (pinfunction "PD1_7") (pintype "bidirectional"))
    )
    (net (code "287") (name "unconnected-(IC4-PD6-Pad12)") (class "Default")
      (node (ref "IC4") (pin "12") (pinfunction "PD6_12") (pintype "bidirectional"))
    )
    (net (code "288") (name "unconnected-(X6-Pad4)") (class "Default")
      (node (ref "X6") (pin "4") (pinfunction "4_4") (pintype "passive"))
    )
  )
)
